# BPB_FM1.net
KiCad netlist of a schematic drawn in EAGLE
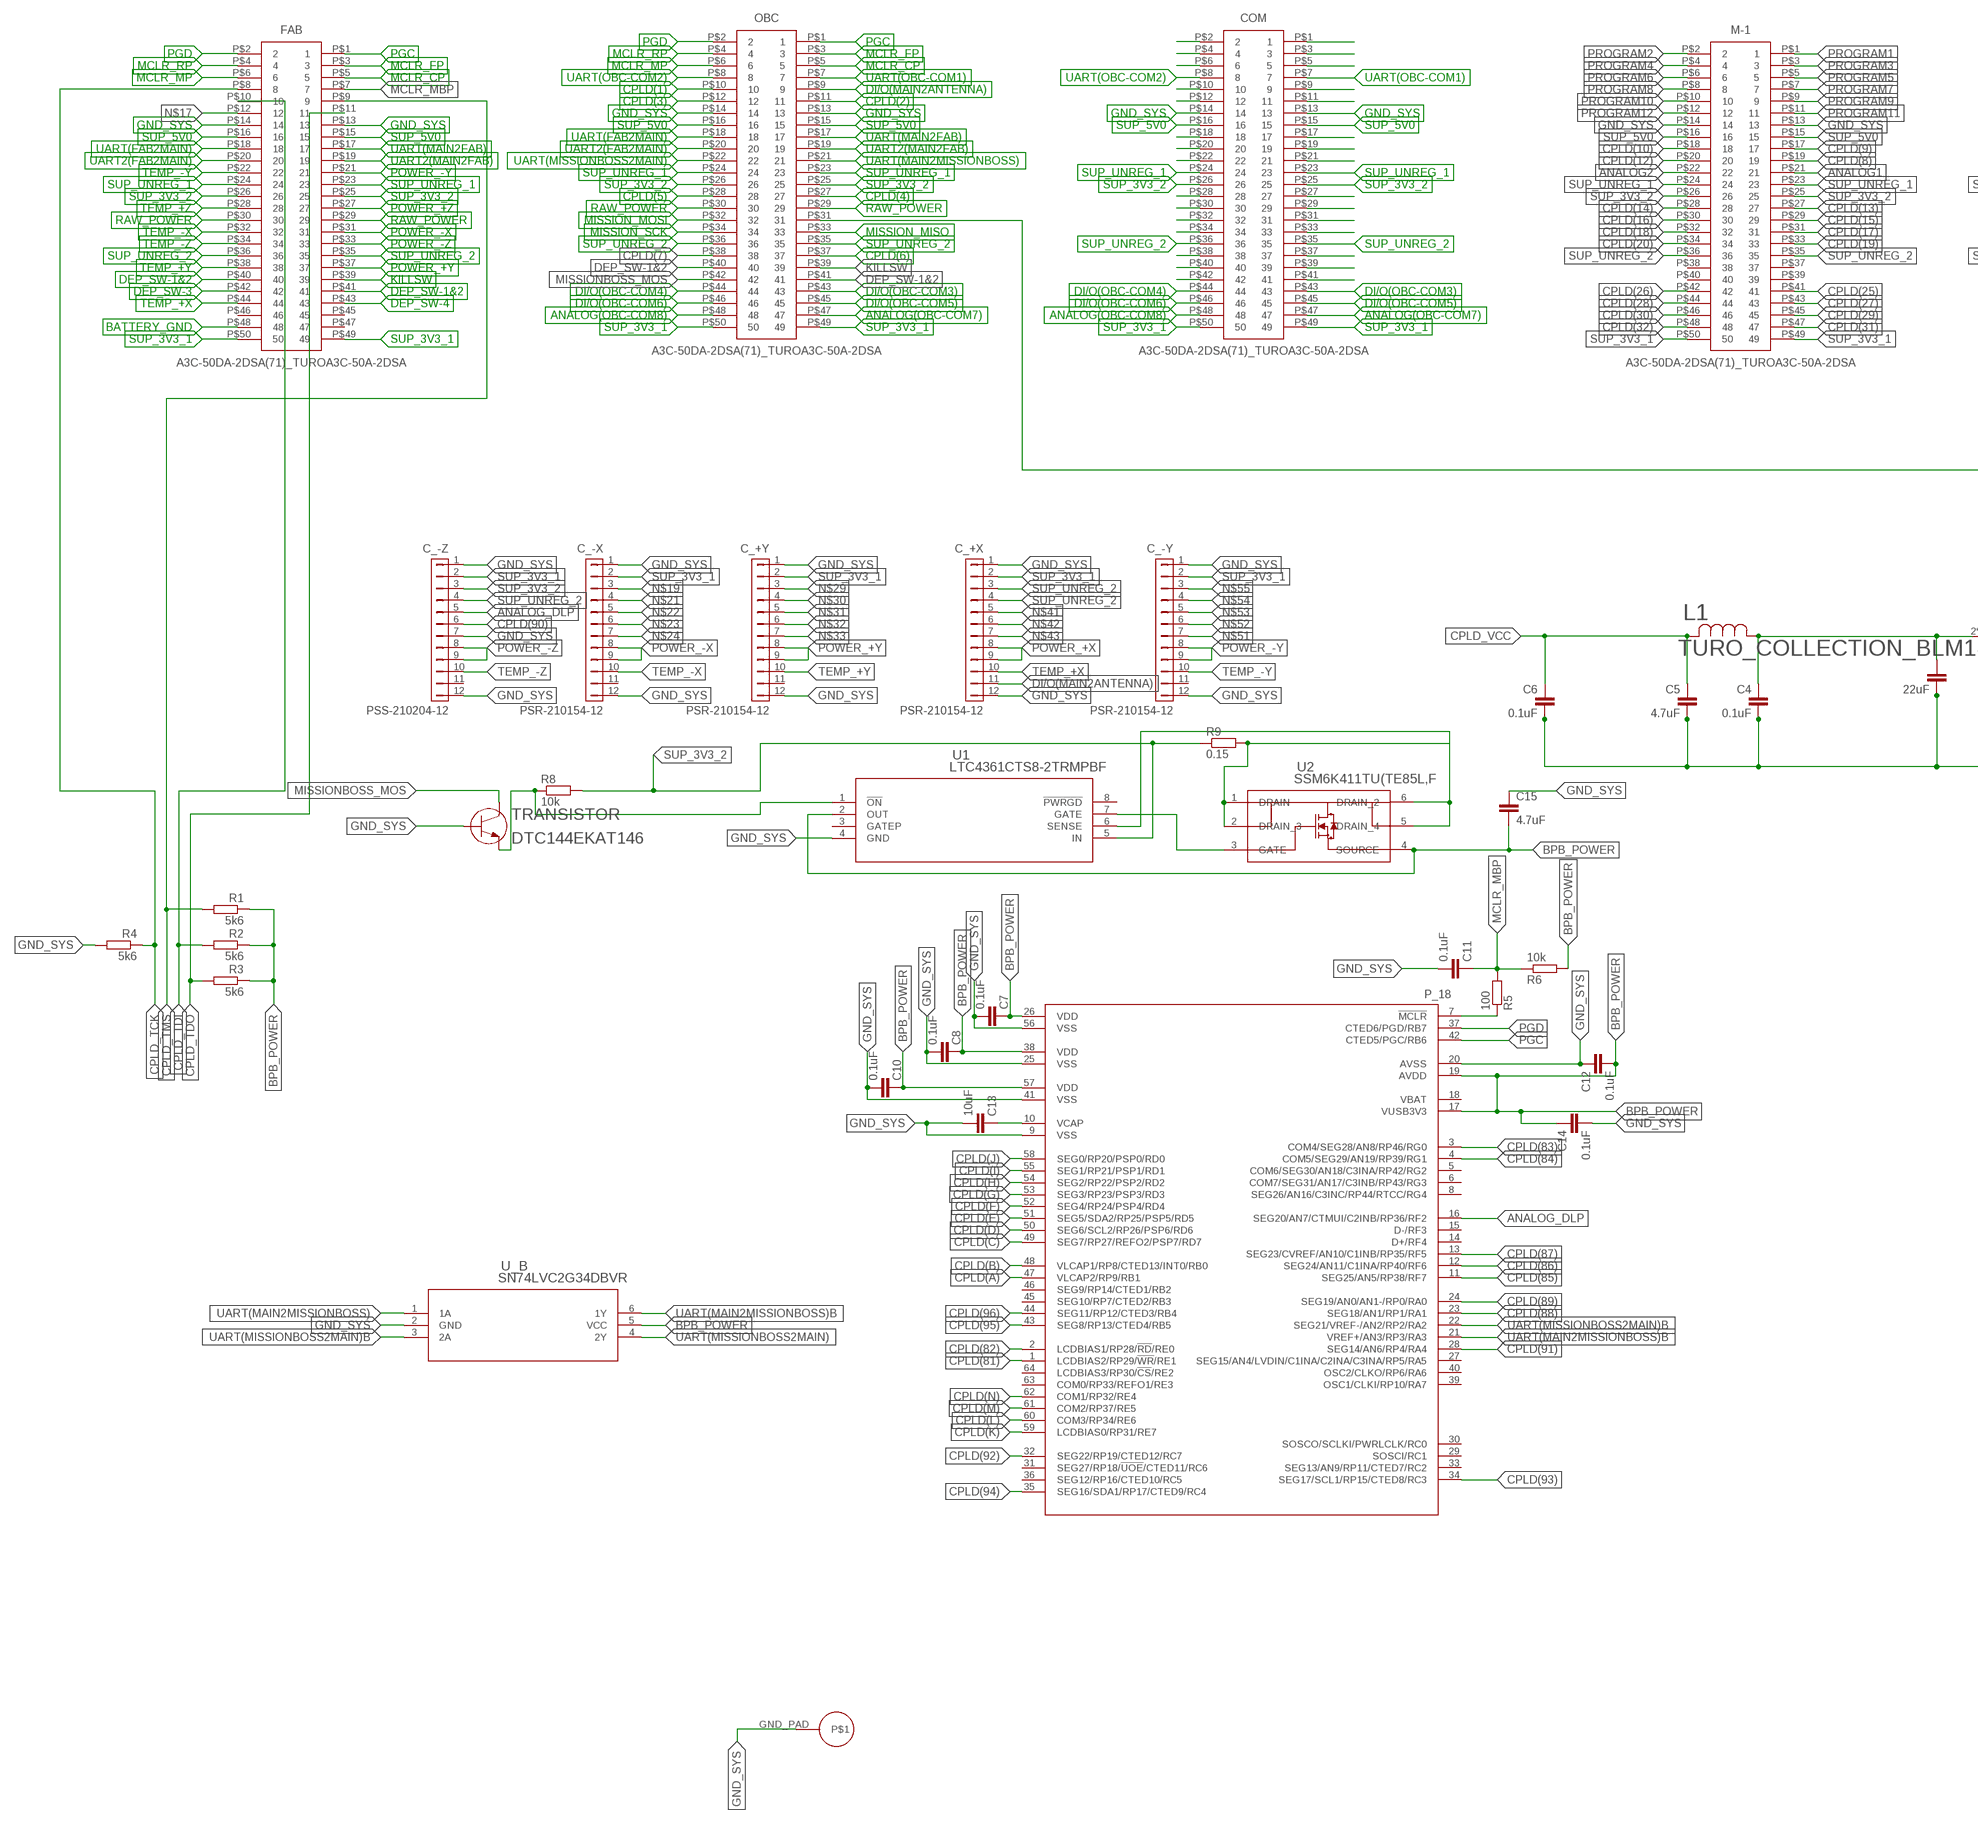
[diagram p0: schematic, sheet 1, part 1 of 2]
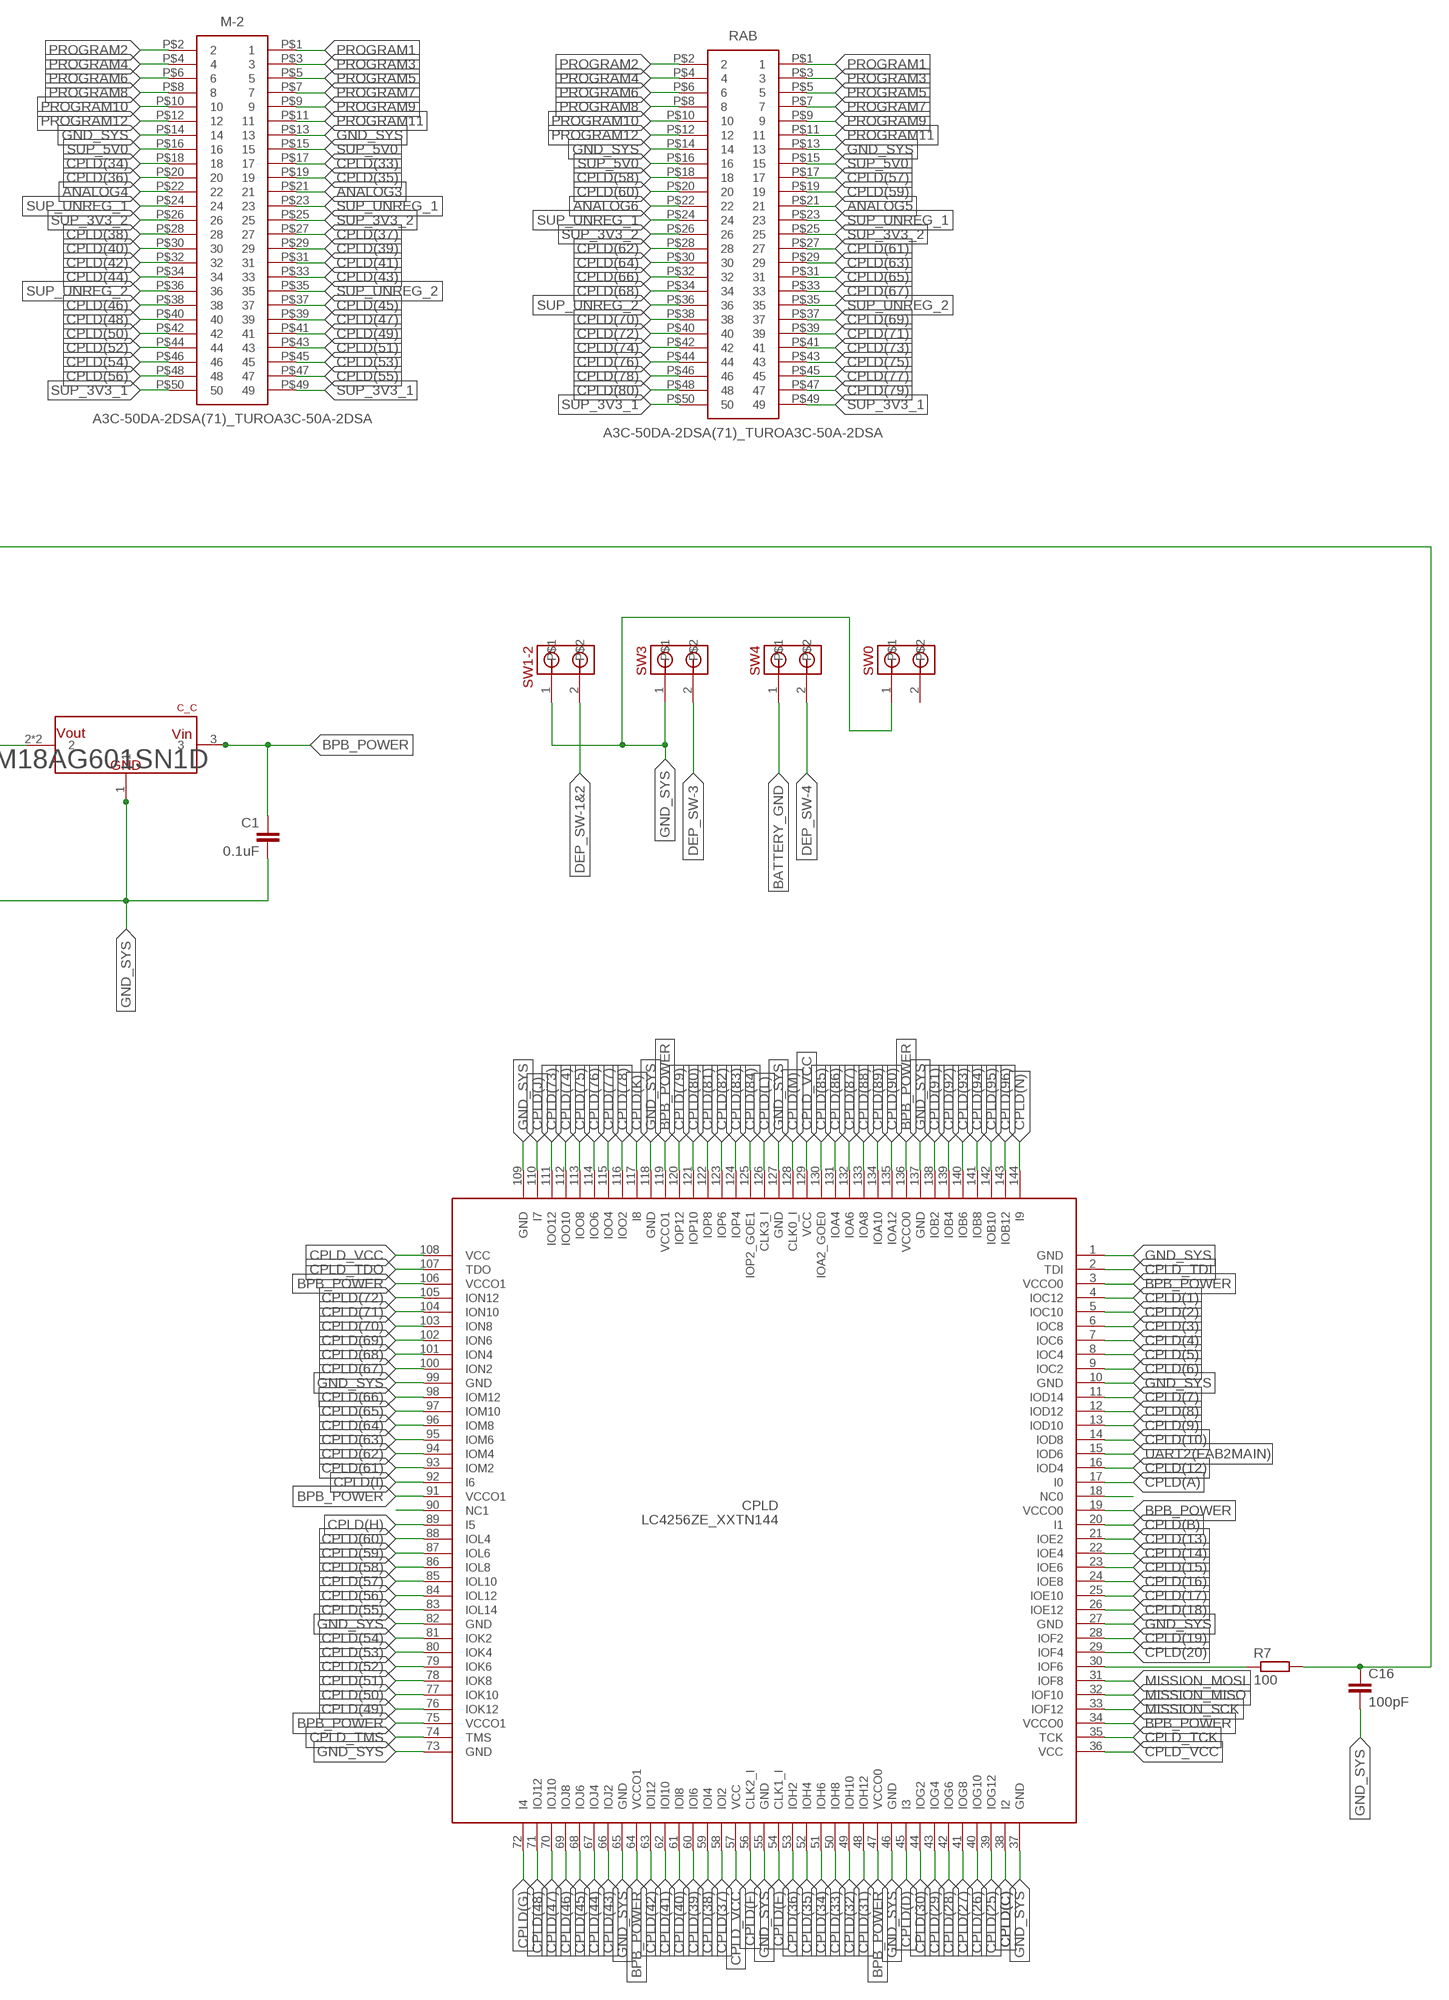
[diagram p1: schematic, sheet 1, part 2 of 2]

(export (version "E")
  (design (tool "Eeschema 10.0.6"))
  (components
    (comp (ref "C1")
      (value "0.1uF")
      (footprint "eagle-import:C0402")
      (libsource (lib "eagle-import") (part "CC0402"))
    )
    (comp (ref "C3")
      (value "22uF")
      (footprint "eagle-import:C2012")
      (libsource (lib "eagle-import") (part "CC2012"))
    )
    (comp (ref "C4")
      (value "0.1uF")
      (footprint "eagle-import:C0402")
      (libsource (lib "eagle-import") (part "CC0402"))
    )
    (comp (ref "C5")
      (value "4.7uF")
      (footprint "eagle-import:C2012")
      (libsource (lib "eagle-import") (part "CC2012"))
    )
    (comp (ref "C6")
      (value "0.1uF")
      (footprint "eagle-import:C0402")
      (libsource (lib "eagle-import") (part "CC0402"))
    )
    (comp (ref "C7")
      (value "0.1uF")
      (footprint "eagle-import:C0402")
      (libsource (lib "eagle-import") (part "CC0402"))
    )
    (comp (ref "C8")
      (value "0.1uF")
      (footprint "eagle-import:C0402")
      (libsource (lib "eagle-import") (part "CC0402"))
    )
    (comp (ref "C10")
      (value "0.1uF")
      (footprint "eagle-import:C0402")
      (libsource (lib "eagle-import") (part "CC0402"))
    )
    (comp (ref "C11")
      (value "0.1uF")
      (footprint "eagle-import:C0402")
      (libsource (lib "eagle-import") (part "CC0402"))
    )
    (comp (ref "C12")
      (value "0.1uF")
      (footprint "eagle-import:C0402")
      (libsource (lib "eagle-import") (part "CC0402"))
    )
    (comp (ref "C13")
      (value "10uF")
      (footprint "eagle-import:C0402")
      (libsource (lib "eagle-import") (part "CC0402"))
    )
    (comp (ref "C14")
      (value "0.1uF")
      (footprint "eagle-import:C0402")
      (libsource (lib "eagle-import") (part "CC0402"))
    )
    (comp (ref "C15")
      (value "4.7uF")
      (footprint "eagle-import:C0402")
      (libsource (lib "eagle-import") (part "CC0402"))
    )
    (comp (ref "C16")
      (value "100pF")
      (footprint "eagle-import:C0402")
      (libsource (lib "eagle-import") (part "CC0402"))
    )
    (comp (ref "COM")
      (value "A3C-50DA-2DSA(71)_TUROA3C-50A-2DSA")
      (footprint "eagle-import:SHDR50W60P200_2X25_5000X400X44_TR")
      (libsource (lib "eagle-import") (part "A3C-50DA-2DSA(71)_TUROA3C-50A-2DSA"))
    )
    (comp (ref "CPLD")
      (value "LC4256ZE_XXTN144")
      (footprint "eagle-import:TQFP144")
      (libsource (lib "eagle-import") (part "LC4256ZE_XXTN144"))
    )
    (comp (ref "C_+X")
      (value "PSR-210154-12")
      (footprint "eagle-import:PIN1X12_90")
      (libsource (lib "eagle-import") (part "PSR-210154-12"))
    )
    (comp (ref "C_+Y")
      (value "PSR-210154-12")
      (footprint "eagle-import:PIN1X12_90")
      (libsource (lib "eagle-import") (part "PSR-210154-12"))
    )
    (comp (ref "C_-X")
      (value "PSR-210154-12")
      (footprint "eagle-import:PIN1X12_90")
      (libsource (lib "eagle-import") (part "PSR-210154-12"))
    )
    (comp (ref "C_-Y")
      (value "PSR-210154-12")
      (footprint "eagle-import:PIN1X12_90")
      (libsource (lib "eagle-import") (part "PSR-210154-12"))
    )
    (comp (ref "C_-Z")
      (value "PSS-210204-12")
      (footprint "eagle-import:PIN1X12")
      (libsource (lib "eagle-import") (part "PSS-210204-12"))
    )
    (comp (ref "C_C")
      (value "NCV1117ST18T3G")
      (footprint "eagle-import:SOT223")
      (libsource (lib "eagle-import") (part "NCV1117ST18T3G"))
    )
    (comp (ref "FAB")
      (value "A3C-50DA-2DSA(71)_TUROA3C-50A-2DSA")
      (footprint "eagle-import:SHDR50W60P200_2X25_5000X400X44_TR")
      (libsource (lib "eagle-import") (part "A3C-50DA-2DSA(71)_TUROA3C-50A-2DSA"))
    )
    (comp (ref "L1")
      (value "TURO_COLLECTION_BLM18AG601SN1D")
      (footprint "eagle-import:TURO_COLLECTION_IND_BLM18_0603")
      (fields (field (name "MANUFACTURER_PART_NUMBER") "BLM18AG601SN1D"))
      (libsource (lib "eagle-import") (part "TURO_COLLECTION_BLM18AG601SN1D"))
    )
    (comp (ref "M-1")
      (value "A3C-50DA-2DSA(71)_TUROA3C-50A-2DSA")
      (footprint "eagle-import:SHDR50W60P200_2X25_5000X400X44_TR")
      (libsource (lib "eagle-import") (part "A3C-50DA-2DSA(71)_TUROA3C-50A-2DSA"))
    )
    (comp (ref "M-2")
      (value "A3C-50DA-2DSA(71)_TUROA3C-50A-2DSA")
      (footprint "eagle-import:SHDR50W60P200_2X25_5000X400X44_TR")
      (libsource (lib "eagle-import") (part "A3C-50DA-2DSA(71)_TUROA3C-50A-2DSA"))
    )
    (comp (ref "OBC")
      (value "A3C-50DA-2DSA(71)_TUROA3C-50A-2DSA")
      (footprint "eagle-import:SHDR50W60P200_2X25_5000X400X44_TR")
      (libsource (lib "eagle-import") (part "A3C-50DA-2DSA(71)_TUROA3C-50A-2DSA"))
    )
    (comp (ref "P_18")
      (value "PIC18F67J94")
      (footprint "eagle-import:PIC18F67J9_SMA_LEAD")
      (libsource (lib "eagle-import") (part "PIC18F67J94"))
    )
    (comp (ref "R1")
      (value "5k6")
      (footprint "eagle-import:R0402")
      (libsource (lib "eagle-import") (part "RR0402"))
    )
    (comp (ref "R2")
      (value "5k6")
      (footprint "eagle-import:R0402")
      (libsource (lib "eagle-import") (part "RR0402"))
    )
    (comp (ref "R3")
      (value "5k6")
      (footprint "eagle-import:R0402")
      (libsource (lib "eagle-import") (part "RR0402"))
    )
    (comp (ref "R4")
      (value "5k6")
      (footprint "eagle-import:R0402")
      (libsource (lib "eagle-import") (part "RR0402"))
    )
    (comp (ref "R5")
      (value "100")
      (footprint "eagle-import:R0402")
      (libsource (lib "eagle-import") (part "RR0402"))
    )
    (comp (ref "R6")
      (value "10k")
      (footprint "eagle-import:R0402")
      (libsource (lib "eagle-import") (part "RR0402"))
    )
    (comp (ref "R7")
      (value "100")
      (footprint "eagle-import:R0402")
      (libsource (lib "eagle-import") (part "RR0402"))
    )
    (comp (ref "R8")
      (value "10k")
      (footprint "eagle-import:R0402")
      (libsource (lib "eagle-import") (part "RR0402"))
    )
    (comp (ref "R9")
      (value "0.15")
      (footprint "eagle-import:R0402")
      (libsource (lib "eagle-import") (part "RR0402"))
    )
    (comp (ref "RAB")
      (value "A3C-50DA-2DSA(71)_TUROA3C-50A-2DSA")
      (footprint "eagle-import:SHDR50W60P200_2X25_5000X400X44_TR")
      (libsource (lib "eagle-import") (part "A3C-50DA-2DSA(71)_TUROA3C-50A-2DSA"))
    )
    (comp (ref "SW0")
      (value "MOLEX-CONN-2-0554600272")
      (footprint "eagle-import:MOLEX-CONN-2-BIRDS")
      (libsource (lib "eagle-import") (part "MOLEX-CONN-2-0554600272"))
    )
    (comp (ref "SW1-2")
      (value "MOLEX-CONN-2-0554600272")
      (footprint "eagle-import:MOLEX-CONN-2-BIRDS")
      (libsource (lib "eagle-import") (part "MOLEX-CONN-2-0554600272"))
    )
    (comp (ref "SW3")
      (value "MOLEX-CONN-2-0554600272")
      (footprint "eagle-import:MOLEX-CONN-2-BIRDS")
      (libsource (lib "eagle-import") (part "MOLEX-CONN-2-0554600272"))
    )
    (comp (ref "SW4")
      (value "MOLEX-CONN-2-0554600272")
      (footprint "eagle-import:MOLEX-CONN-2-BIRDS")
      (libsource (lib "eagle-import") (part "MOLEX-CONN-2-0554600272"))
    )
    (comp (ref "TRANSISTOR")
      (value "DTC144EKAT146")
      (footprint "eagle-import:TRANS_DTA113TKAT_ROM")
      (fields (field (name "COPYRIGHT") "Copyright (C) 2018 Accelerated Designs. All rights reserved"))
      (libsource (lib "eagle-import") (part "DTC144EKAT146"))
    )
    (comp (ref "U$1")
      (value "GND_PAD")
      (footprint "eagle-import:GND_PAD")
      (libsource (lib "eagle-import") (part "GND_PAD"))
    )
    (comp (ref "U1")
      (value "LTC4361CTS8-2TRMPBF")
      (footprint "eagle-import:TSOT-23_TS8_LIT")
      (fields (field (name "MANUFACTURER_PART_NUMBER") "LTC4361CTS8-2#TRMPBF"))
      (libsource (lib "eagle-import") (part "LTC4361CTS8-2TRMPBF"))
    )
    (comp (ref "U2")
      (value "SSM6K411TU(TE85L,F")
      (footprint "eagle-import:SON_E85L,F_TOS")
      (fields (field (name "COPYRIGHT") "Copyright (C) 2018 Accelerated Designs. All rights reserved"))
      (libsource (lib "eagle-import") (part "SSM6K411TU(TE85L,F"))
    )
    (comp (ref "U_B")
      (value "SN74LVC2G34DBVR")
      (footprint "eagle-import:DBV6")
      (fields
        (field (name "GENERIC_PART_NUMBER") "SN74LVC2G34")
        (field (name "MANUFACTURER") "Texas Instruments")
      )
      (libsource (lib "eagle-import") (part "SN74LVC2G34DBVR"))
    )
  )
  (nets
    (net (code "1") (name "ANALOG(OBC-COM7)") (class "Default")
      (node (ref "COM") (pin "P$47") (pinfunction "47_P$47") (pintype "passive"))
      (node (ref "OBC") (pin "P$47") (pinfunction "47_P$47") (pintype "passive"))
    )
    (net (code "2") (name "ANALOG(OBC-COM8)") (class "Default")
      (node (ref "COM") (pin "P$48") (pinfunction "48_P$48") (pintype "passive"))
      (node (ref "OBC") (pin "P$48") (pinfunction "48_P$48") (pintype "passive"))
    )
    (net (code "3") (name "ANALOG1") (class "Default")
      (node (ref "M-1") (pin "P$21") (pinfunction "21_P$21") (pintype "passive"))
    )
    (net (code "4") (name "ANALOG2") (class "Default")
      (node (ref "M-1") (pin "P$22") (pinfunction "22_P$22") (pintype "passive"))
    )
    (net (code "5") (name "ANALOG3") (class "Default")
      (node (ref "M-2") (pin "P$21") (pinfunction "21_P$21") (pintype "passive"))
    )
    (net (code "6") (name "ANALOG4") (class "Default")
      (node (ref "M-2") (pin "P$22") (pinfunction "22_P$22") (pintype "passive"))
    )
    (net (code "7") (name "ANALOG5") (class "Default")
      (node (ref "RAB") (pin "P$21") (pinfunction "21_P$21") (pintype "passive"))
    )
    (net (code "8") (name "ANALOG6") (class "Default")
      (node (ref "RAB") (pin "P$22") (pinfunction "22_P$22") (pintype "passive"))
    )
    (net (code "9") (name "ANALOG_DLP") (class "Default")
      (node (ref "C_-Z") (pin "5") (pinfunction "5_5") (pintype "passive"))
      (node (ref "P_18") (pin "16") (pinfunction "SEG20/AN7/CTMUI/C2INB/RP36/RF2_16") (pintype "bidirectional"))
    )
    (net (code "10") (name "BATTERY_GND") (class "Default")
      (node (ref "FAB") (pin "P$48") (pinfunction "48_P$48") (pintype "passive"))
      (node (ref "SW4") (pin "1") (pinfunction "P$1_1") (pintype "bidirectional"))
    )
    (net (code "11") (name "BPB_POWER") (class "Default")
      (node (ref "C1") (pin "1") (pinfunction "1_1") (pintype "passive"))
      (node (ref "C10") (pin "1") (pinfunction "1_1") (pintype "passive"))
      (node (ref "C12") (pin "2") (pinfunction "2_2") (pintype "passive"))
      (node (ref "C14") (pin "1") (pinfunction "1_1") (pintype "passive"))
      (node (ref "C15") (pin "2") (pinfunction "2_2") (pintype "passive"))
      (node (ref "C7") (pin "1") (pinfunction "1_1") (pintype "passive"))
      (node (ref "C8") (pin "1") (pinfunction "1_1") (pintype "passive"))
      (node (ref "CPLD") (pin "106") (pinfunction "VCCO1_106") (pintype "power_in"))
      (node (ref "CPLD") (pin "119") (pinfunction "VCCO1_119") (pintype "power_in"))
      (node (ref "CPLD") (pin "136") (pinfunction "VCCO0_136") (pintype "power_in"))
      (node (ref "CPLD") (pin "19") (pinfunction "VCCO0_19") (pintype "power_in"))
      (node (ref "CPLD") (pin "3") (pinfunction "VCCO0_3") (pintype "power_in"))
      (node (ref "CPLD") (pin "34") (pinfunction "VCCO0_34") (pintype "power_in"))
      (node (ref "CPLD") (pin "47") (pinfunction "VCCO0_47") (pintype "power_in"))
      (node (ref "CPLD") (pin "64") (pinfunction "VCCO1_64") (pintype "power_in"))
      (node (ref "CPLD") (pin "75") (pinfunction "VCCO1_75") (pintype "power_in"))
      (node (ref "CPLD") (pin "91") (pinfunction "VCCO1_91") (pintype "power_in"))
      (node (ref "C_C") (pin "3") (pinfunction "3_3") (pintype "bidirectional"))
      (node (ref "P_18") (pin "17") (pinfunction "VUSB3V3_17") (pintype "bidirectional"))
      (node (ref "P_18") (pin "19") (pinfunction "AVDD_19") (pintype "bidirectional"))
      (node (ref "P_18") (pin "26") (pinfunction "VDD_26") (pintype "bidirectional"))
      (node (ref "P_18") (pin "38") (pinfunction "VDD_38") (pintype "bidirectional"))
      (node (ref "P_18") (pin "57") (pinfunction "VDD_57") (pintype "bidirectional"))
      (node (ref "R1") (pin "1") (pinfunction "1_1") (pintype "passive"))
      (node (ref "R2") (pin "1") (pinfunction "1_1") (pintype "passive"))
      (node (ref "R3") (pin "1") (pinfunction "1_1") (pintype "passive"))
      (node (ref "R6") (pin "2") (pinfunction "2_2") (pintype "passive"))
      (node (ref "U1") (pin "2") (pinfunction "OUT_2") (pintype "output"))
      (node (ref "U2") (pin "4") (pinfunction "SOURCE_4") (pintype "passive"))
      (node (ref "U_B") (pin "5") (pinfunction "VCC_5") (pintype "power_in"))
    )
    (net (code "12") (name "CPLD(1)") (class "Default")
      (node (ref "CPLD") (pin "4") (pinfunction "IOC12_4") (pintype "bidirectional"))
      (node (ref "OBC") (pin "P$10") (pinfunction "10_P$10") (pintype "passive"))
    )
    (net (code "13") (name "CPLD(2)") (class "Default")
      (node (ref "CPLD") (pin "5") (pinfunction "IOC10_5") (pintype "bidirectional"))
      (node (ref "OBC") (pin "P$11") (pinfunction "11_P$11") (pintype "passive"))
    )
    (net (code "14") (name "CPLD(3)") (class "Default")
      (node (ref "CPLD") (pin "6") (pinfunction "IOC8_6") (pintype "bidirectional"))
      (node (ref "OBC") (pin "P$12") (pinfunction "12_P$12") (pintype "passive"))
    )
    (net (code "15") (name "CPLD(4)") (class "Default")
      (node (ref "CPLD") (pin "7") (pinfunction "IOC6_7") (pintype "bidirectional"))
      (node (ref "OBC") (pin "P$27") (pinfunction "27_P$27") (pintype "passive"))
    )
    (net (code "16") (name "CPLD(5)") (class "Default")
      (node (ref "CPLD") (pin "8") (pinfunction "IOC4_8") (pintype "bidirectional"))
      (node (ref "OBC") (pin "P$28") (pinfunction "28_P$28") (pintype "passive"))
    )
    (net (code "17") (name "CPLD(6)") (class "Default")
      (node (ref "CPLD") (pin "9") (pinfunction "IOC2_9") (pintype "bidirectional"))
      (node (ref "OBC") (pin "P$37") (pinfunction "37_P$37") (pintype "passive"))
    )
    (net (code "18") (name "CPLD(7)") (class "Default")
      (node (ref "CPLD") (pin "11") (pinfunction "IOD14_11") (pintype "bidirectional"))
      (node (ref "OBC") (pin "P$38") (pinfunction "38_P$38") (pintype "passive"))
    )
    (net (code "19") (name "CPLD(8)") (class "Default")
      (node (ref "CPLD") (pin "12") (pinfunction "IOD12_12") (pintype "bidirectional"))
      (node (ref "M-1") (pin "P$19") (pinfunction "19_P$19") (pintype "passive"))
    )
    (net (code "20") (name "CPLD(9)") (class "Default")
      (node (ref "CPLD") (pin "13") (pinfunction "IOD10_13") (pintype "bidirectional"))
      (node (ref "M-1") (pin "P$17") (pinfunction "17_P$17") (pintype "passive"))
    )
    (net (code "21") (name "CPLD(10)") (class "Default")
      (node (ref "CPLD") (pin "14") (pinfunction "IOD8_14") (pintype "bidirectional"))
      (node (ref "M-1") (pin "P$18") (pinfunction "18_P$18") (pintype "passive"))
    )
    (net (code "22") (name "CPLD(12)") (class "Default")
      (node (ref "CPLD") (pin "16") (pinfunction "IOD4_16") (pintype "bidirectional"))
      (node (ref "M-1") (pin "P$20") (pinfunction "20_P$20") (pintype "passive"))
    )
    (net (code "23") (name "CPLD(13)") (class "Default")
      (node (ref "CPLD") (pin "21") (pinfunction "IOE2_21") (pintype "bidirectional"))
      (node (ref "M-1") (pin "P$27") (pinfunction "27_P$27") (pintype "passive"))
    )
    (net (code "24") (name "CPLD(14)") (class "Default")
      (node (ref "CPLD") (pin "22") (pinfunction "IOE4_22") (pintype "bidirectional"))
      (node (ref "M-1") (pin "P$28") (pinfunction "28_P$28") (pintype "passive"))
    )
    (net (code "25") (name "CPLD(15)") (class "Default")
      (node (ref "CPLD") (pin "23") (pinfunction "IOE6_23") (pintype "bidirectional"))
      (node (ref "M-1") (pin "P$29") (pinfunction "29_P$29") (pintype "passive"))
    )
    (net (code "26") (name "CPLD(16)") (class "Default")
      (node (ref "CPLD") (pin "24") (pinfunction "IOE8_24") (pintype "bidirectional"))
      (node (ref "M-1") (pin "P$30") (pinfunction "30_P$30") (pintype "passive"))
    )
    (net (code "27") (name "CPLD(17)") (class "Default")
      (node (ref "CPLD") (pin "25") (pinfunction "IOE10_25") (pintype "bidirectional"))
      (node (ref "M-1") (pin "P$31") (pinfunction "31_P$31") (pintype "passive"))
    )
    (net (code "28") (name "CPLD(18)") (class "Default")
      (node (ref "CPLD") (pin "26") (pinfunction "IOE12_26") (pintype "bidirectional"))
      (node (ref "M-1") (pin "P$32") (pinfunction "32_P$32") (pintype "passive"))
    )
    (net (code "29") (name "CPLD(19)") (class "Default")
      (node (ref "CPLD") (pin "28") (pinfunction "IOF2_28") (pintype "bidirectional"))
      (node (ref "M-1") (pin "P$33") (pinfunction "33_P$33") (pintype "passive"))
    )
    (net (code "30") (name "CPLD(20)") (class "Default")
      (node (ref "CPLD") (pin "29") (pinfunction "IOF4_29") (pintype "bidirectional"))
      (node (ref "M-1") (pin "P$34") (pinfunction "34_P$34") (pintype "passive"))
    )
    (net (code "31") (name "CPLD(25)") (class "Default")
      (node (ref "CPLD") (pin "39") (pinfunction "IOG12_39") (pintype "bidirectional"))
      (node (ref "M-1") (pin "P$41") (pinfunction "41_P$41") (pintype "passive"))
    )
    (net (code "32") (name "CPLD(26)") (class "Default")
      (node (ref "CPLD") (pin "40") (pinfunction "IOG10_40") (pintype "bidirectional"))
      (node (ref "M-1") (pin "P$42") (pinfunction "42_P$42") (pintype "passive"))
    )
    (net (code "33") (name "CPLD(27)") (class "Default")
      (node (ref "CPLD") (pin "41") (pinfunction "IOG8_41") (pintype "bidirectional"))
      (node (ref "M-1") (pin "P$43") (pinfunction "43_P$43") (pintype "passive"))
    )
    (net (code "34") (name "CPLD(28)") (class "Default")
      (node (ref "CPLD") (pin "42") (pinfunction "IOG6_42") (pintype "bidirectional"))
      (node (ref "M-1") (pin "P$44") (pinfunction "44_P$44") (pintype "passive"))
    )
    (net (code "35") (name "CPLD(29)") (class "Default")
      (node (ref "CPLD") (pin "43") (pinfunction "IOG4_43") (pintype "bidirectional"))
      (node (ref "M-1") (pin "P$45") (pinfunction "45_P$45") (pintype "passive"))
    )
    (net (code "36") (name "CPLD(30)") (class "Default")
      (node (ref "CPLD") (pin "44") (pinfunction "IOG2_44") (pintype "bidirectional"))
      (node (ref "M-1") (pin "P$46") (pinfunction "46_P$46") (pintype "passive"))
    )
    (net (code "37") (name "CPLD(31)") (class "Default")
      (node (ref "CPLD") (pin "48") (pinfunction "IOH12_48") (pintype "bidirectional"))
      (node (ref "M-1") (pin "P$47") (pinfunction "47_P$47") (pintype "passive"))
    )
    (net (code "38") (name "CPLD(32)") (class "Default")
      (node (ref "CPLD") (pin "49") (pinfunction "IOH10_49") (pintype "bidirectional"))
      (node (ref "M-1") (pin "P$48") (pinfunction "48_P$48") (pintype "passive"))
    )
    (net (code "39") (name "CPLD(33)") (class "Default")
      (node (ref "CPLD") (pin "50") (pinfunction "IOH8_50") (pintype "bidirectional"))
      (node (ref "M-2") (pin "P$17") (pinfunction "17_P$17") (pintype "passive"))
    )
    (net (code "40") (name "CPLD(34)") (class "Default")
      (node (ref "CPLD") (pin "51") (pinfunction "IOH6_51") (pintype "bidirectional"))
      (node (ref "M-2") (pin "P$18") (pinfunction "18_P$18") (pintype "passive"))
    )
    (net (code "41") (name "CPLD(35)") (class "Default")
      (node (ref "CPLD") (pin "52") (pinfunction "IOH4_52") (pintype "bidirectional"))
      (node (ref "M-2") (pin "P$19") (pinfunction "19_P$19") (pintype "passive"))
    )
    (net (code "42") (name "CPLD(36)") (class "Default")
      (node (ref "CPLD") (pin "53") (pinfunction "IOH2_53") (pintype "bidirectional"))
      (node (ref "M-2") (pin "P$20") (pinfunction "20_P$20") (pintype "passive"))
    )
    (net (code "43") (name "CPLD(37)") (class "Default")
      (node (ref "CPLD") (pin "58") (pinfunction "IOI2_58") (pintype "bidirectional"))
      (node (ref "M-2") (pin "P$27") (pinfunction "27_P$27") (pintype "passive"))
    )
    (net (code "44") (name "CPLD(38)") (class "Default")
      (node (ref "CPLD") (pin "59") (pinfunction "IOI4_59") (pintype "bidirectional"))
      (node (ref "M-2") (pin "P$28") (pinfunction "28_P$28") (pintype "passive"))
    )
    (net (code "45") (name "CPLD(39)") (class "Default")
      (node (ref "CPLD") (pin "60") (pinfunction "IOI6_60") (pintype "bidirectional"))
      (node (ref "M-2") (pin "P$29") (pinfunction "29_P$29") (pintype "passive"))
    )
    (net (code "46") (name "CPLD(40)") (class "Default")
      (node (ref "CPLD") (pin "61") (pinfunction "IOI8_61") (pintype "bidirectional"))
      (node (ref "M-2") (pin "P$30") (pinfunction "30_P$30") (pintype "passive"))
    )
    (net (code "47") (name "CPLD(41)") (class "Default")
      (node (ref "CPLD") (pin "62") (pinfunction "IOI10_62") (pintype "bidirectional"))
      (node (ref "M-2") (pin "P$31") (pinfunction "31_P$31") (pintype "passive"))
    )
    (net (code "48") (name "CPLD(42)") (class "Default")
      (node (ref "CPLD") (pin "63") (pinfunction "IOI12_63") (pintype "bidirectional"))
      (node (ref "M-2") (pin "P$32") (pinfunction "32_P$32") (pintype "passive"))
    )
    (net (code "49") (name "CPLD(43)") (class "Default")
      (node (ref "CPLD") (pin "66") (pinfunction "IOJ2_66") (pintype "bidirectional"))
      (node (ref "M-2") (pin "P$33") (pinfunction "33_P$33") (pintype "passive"))
    )
    (net (code "50") (name "CPLD(44)") (class "Default")
      (node (ref "CPLD") (pin "67") (pinfunction "IOJ4_67") (pintype "bidirectional"))
      (node (ref "M-2") (pin "P$34") (pinfunction "34_P$34") (pintype "passive"))
    )
    (net (code "51") (name "CPLD(45)") (class "Default")
      (node (ref "CPLD") (pin "68") (pinfunction "IOJ6_68") (pintype "bidirectional"))
      (node (ref "M-2") (pin "P$37") (pinfunction "37_P$37") (pintype "passive"))
    )
    (net (code "52") (name "CPLD(46)") (class "Default")
      (node (ref "CPLD") (pin "69") (pinfunction "IOJ8_69") (pintype "bidirectional"))
      (node (ref "M-2") (pin "P$38") (pinfunction "38_P$38") (pintype "passive"))
    )
    (net (code "53") (name "CPLD(47)") (class "Default")
      (node (ref "CPLD") (pin "70") (pinfunction "IOJ10_70") (pintype "bidirectional"))
      (node (ref "M-2") (pin "P$39") (pinfunction "39_P$39") (pintype "passive"))
    )
    (net (code "54") (name "CPLD(48)") (class "Default")
      (node (ref "CPLD") (pin "71") (pinfunction "IOJ12_71") (pintype "bidirectional"))
      (node (ref "M-2") (pin "P$40") (pinfunction "40_P$40") (pintype "passive"))
    )
    (net (code "55") (name "CPLD(49)") (class "Default")
      (node (ref "CPLD") (pin "76") (pinfunction "IOK12_76") (pintype "bidirectional"))
      (node (ref "M-2") (pin "P$41") (pinfunction "41_P$41") (pintype "passive"))
    )
    (net (code "56") (name "CPLD(50)") (class "Default")
      (node (ref "CPLD") (pin "77") (pinfunction "IOK10_77") (pintype "bidirectional"))
      (node (ref "M-2") (pin "P$42") (pinfunction "42_P$42") (pintype "passive"))
    )
    (net (code "57") (name "CPLD(51)") (class "Default")
      (node (ref "CPLD") (pin "78") (pinfunction "IOK8_78") (pintype "bidirectional"))
      (node (ref "M-2") (pin "P$43") (pinfunction "43_P$43") (pintype "passive"))
    )
    (net (code "58") (name "CPLD(52)") (class "Default")
      (node (ref "CPLD") (pin "79") (pinfunction "IOK6_79") (pintype "bidirectional"))
      (node (ref "M-2") (pin "P$44") (pinfunction "44_P$44") (pintype "passive"))
    )
    (net (code "59") (name "CPLD(53)") (class "Default")
      (node (ref "CPLD") (pin "80") (pinfunction "IOK4_80") (pintype "bidirectional"))
      (node (ref "M-2") (pin "P$45") (pinfunction "45_P$45") (pintype "passive"))
    )
    (net (code "60") (name "CPLD(54)") (class "Default")
      (node (ref "CPLD") (pin "81") (pinfunction "IOK2_81") (pintype "bidirectional"))
      (node (ref "M-2") (pin "P$46") (pinfunction "46_P$46") (pintype "passive"))
    )
    (net (code "61") (name "CPLD(55)") (class "Default")
      (node (ref "CPLD") (pin "83") (pinfunction "IOL14_83") (pintype "bidirectional"))
      (node (ref "M-2") (pin "P$47") (pinfunction "47_P$47") (pintype "passive"))
    )
    (net (code "62") (name "CPLD(56)") (class "Default")
      (node (ref "CPLD") (pin "84") (pinfunction "IOL12_84") (pintype "bidirectional"))
      (node (ref "M-2") (pin "P$48") (pinfunction "48_P$48") (pintype "passive"))
    )
    (net (code "63") (name "CPLD(57)") (class "Default")
      (node (ref "CPLD") (pin "85") (pinfunction "IOL10_85") (pintype "bidirectional"))
      (node (ref "RAB") (pin "P$17") (pinfunction "17_P$17") (pintype "passive"))
    )
    (net (code "64") (name "CPLD(58)") (class "Default")
      (node (ref "CPLD") (pin "86") (pinfunction "IOL8_86") (pintype "bidirectional"))
      (node (ref "RAB") (pin "P$18") (pinfunction "18_P$18") (pintype "passive"))
    )
    (net (code "65") (name "CPLD(59)") (class "Default")
      (node (ref "CPLD") (pin "87") (pinfunction "IOL6_87") (pintype "bidirectional"))
      (node (ref "RAB") (pin "P$19") (pinfunction "19_P$19") (pintype "passive"))
    )
    (net (code "66") (name "CPLD(60)") (class "Default")
      (node (ref "CPLD") (pin "88") (pinfunction "IOL4_88") (pintype "bidirectional"))
      (node (ref "RAB") (pin "P$20") (pinfunction "20_P$20") (pintype "passive"))
    )
    (net (code "67") (name "CPLD(61)") (class "Default")
      (node (ref "CPLD") (pin "93") (pinfunction "IOM2_93") (pintype "bidirectional"))
      (node (ref "RAB") (pin "P$27") (pinfunction "27_P$27") (pintype "passive"))
    )
    (net (code "68") (name "CPLD(62)") (class "Default")
      (node (ref "CPLD") (pin "94") (pinfunction "IOM4_94") (pintype "bidirectional"))
      (node (ref "RAB") (pin "P$28") (pinfunction "28_P$28") (pintype "passive"))
    )
    (net (code "69") (name "CPLD(63)") (class "Default")
      (node (ref "CPLD") (pin "95") (pinfunction "IOM6_95") (pintype "bidirectional"))
      (node (ref "RAB") (pin "P$29") (pinfunction "29_P$29") (pintype "passive"))
    )
    (net (code "70") (name "CPLD(64)") (class "Default")
      (node (ref "CPLD") (pin "96") (pinfunction "IOM8_96") (pintype "bidirectional"))
      (node (ref "RAB") (pin "P$30") (pinfunction "30_P$30") (pintype "passive"))
    )
    (net (code "71") (name "CPLD(65)") (class "Default")
      (node (ref "CPLD") (pin "97") (pinfunction "IOM10_97") (pintype "bidirectional"))
      (node (ref "RAB") (pin "P$31") (pinfunction "31_P$31") (pintype "passive"))
    )
    (net (code "72") (name "CPLD(66)") (class "Default")
      (node (ref "CPLD") (pin "98") (pinfunction "IOM12_98") (pintype "bidirectional"))
      (node (ref "RAB") (pin "P$32") (pinfunction "32_P$32") (pintype "passive"))
    )
    (net (code "73") (name "CPLD(67)") (class "Default")
      (node (ref "CPLD") (pin "100") (pinfunction "ION2_100") (pintype "bidirectional"))
      (node (ref "RAB") (pin "P$33") (pinfunction "33_P$33") (pintype "passive"))
    )
    (net (code "74") (name "CPLD(68)") (class "Default")
      (node (ref "CPLD") (pin "101") (pinfunction "ION4_101") (pintype "bidirectional"))
      (node (ref "RAB") (pin "P$34") (pinfunction "34_P$34") (pintype "passive"))
    )
    (net (code "75") (name "CPLD(69)") (class "Default")
      (node (ref "CPLD") (pin "102") (pinfunction "ION6_102") (pintype "bidirectional"))
      (node (ref "RAB") (pin "P$37") (pinfunction "37_P$37") (pintype "passive"))
    )
    (net (code "76") (name "CPLD(70)") (class "Default")
      (node (ref "CPLD") (pin "103") (pinfunction "ION8_103") (pintype "bidirectional"))
      (node (ref "RAB") (pin "P$38") (pinfunction "38_P$38") (pintype "passive"))
    )
    (net (code "77") (name "CPLD(71)") (class "Default")
      (node (ref "CPLD") (pin "104") (pinfunction "ION10_104") (pintype "bidirectional"))
      (node (ref "RAB") (pin "P$39") (pinfunction "39_P$39") (pintype "passive"))
    )
    (net (code "78") (name "CPLD(72)") (class "Default")
      (node (ref "CPLD") (pin "105") (pinfunction "ION12_105") (pintype "bidirectional"))
      (node (ref "RAB") (pin "P$40") (pinfunction "40_P$40") (pintype "passive"))
    )
    (net (code "79") (name "CPLD(73)") (class "Default")
      (node (ref "CPLD") (pin "111") (pinfunction "IOO12_111") (pintype "bidirectional"))
      (node (ref "RAB") (pin "P$41") (pinfunction "41_P$41") (pintype "passive"))
    )
    (net (code "80") (name "CPLD(74)") (class "Default")
      (node (ref "CPLD") (pin "112") (pinfunction "IOO10_112") (pintype "bidirectional"))
      (node (ref "RAB") (pin "P$42") (pinfunction "42_P$42") (pintype "passive"))
    )
    (net (code "81") (name "CPLD(75)") (class "Default")
      (node (ref "CPLD") (pin "113") (pinfunction "IOO8_113") (pintype "bidirectional"))
      (node (ref "RAB") (pin "P$43") (pinfunction "43_P$43") (pintype "passive"))
    )
    (net (code "82") (name "CPLD(76)") (class "Default")
      (node (ref "CPLD") (pin "114") (pinfunction "IOO6_114") (pintype "bidirectional"))
      (node (ref "RAB") (pin "P$44") (pinfunction "44_P$44") (pintype "passive"))
    )
    (net (code "83") (name "CPLD(77)") (class "Default")
      (node (ref "CPLD") (pin "115") (pinfunction "IOO4_115") (pintype "bidirectional"))
      (node (ref "RAB") (pin "P$45") (pinfunction "45_P$45") (pintype "passive"))
    )
    (net (code "84") (name "CPLD(78)") (class "Default")
      (node (ref "CPLD") (pin "116") (pinfunction "IOO2_116") (pintype "bidirectional"))
      (node (ref "RAB") (pin "P$46") (pinfunction "46_P$46") (pintype "passive"))
    )
    (net (code "85") (name "CPLD(79)") (class "Default")
      (node (ref "CPLD") (pin "120") (pinfunction "IOP12_120") (pintype "bidirectional"))
      (node (ref "RAB") (pin "P$47") (pinfunction "47_P$47") (pintype "passive"))
    )
    (net (code "86") (name "CPLD(80)") (class "Default")
      (node (ref "CPLD") (pin "121") (pinfunction "IOP10_121") (pintype "bidirectional"))
      (node (ref "RAB") (pin "P$48") (pinfunction "48_P$48") (pintype "passive"))
    )
    (net (code "87") (name "CPLD(81)") (class "Default")
      (node (ref "CPLD") (pin "122") (pinfunction "IOP8_122") (pintype "bidirectional"))
      (node (ref "P_18") (pin "1") (pinfunction "LCDBIAS2/RP29/~{WR}/RE1_1") (pintype "bidirectional"))
    )
    (net (code "88") (name "CPLD(82)") (class "Default")
      (node (ref "CPLD") (pin "123") (pinfunction "IOP6_123") (pintype "bidirectional"))
      (node (ref "P_18") (pin "2") (pinfunction "LCDBIAS1/RP28/~{RD}/RE0_2") (pintype "bidirectional"))
    )
    (net (code "89") (name "CPLD(83)") (class "Default")
      (node (ref "CPLD") (pin "124") (pinfunction "IOP4_124") (pintype "bidirectional"))
      (node (ref "P_18") (pin "3") (pinfunction "COM4/SEG28/AN8/RP46/RG0_3") (pintype "bidirectional"))
    )
    (net (code "90") (name "CPLD(84)") (class "Default")
      (node (ref "CPLD") (pin "125") (pinfunction "IOP2_GOE1_125") (pintype "bidirectional"))
      (node (ref "P_18") (pin "4") (pinfunction "COM5/SEG29/AN19/RP39/RG1_4") (pintype "bidirectional"))
    )
    (net (code "91") (name "CPLD(85)") (class "Default")
      (node (ref "CPLD") (pin "130") (pinfunction "IOA2_GOE0_130") (pintype "bidirectional"))
      (node (ref "P_18") (pin "11") (pinfunction "SEG25/AN5/RP38/RF7_11") (pintype "bidirectional"))
    )
    (net (code "92") (name "CPLD(86)") (class "Default")
      (node (ref "CPLD") (pin "131") (pinfunction "IOA4_131") (pintype "bidirectional"))
      (node (ref "P_18") (pin "12") (pinfunction "SEG24/AN11/C1INA/RP40/RF6_12") (pintype "bidirectional"))
    )
    (net (code "93") (name "CPLD(87)") (class "Default")
      (node (ref "CPLD") (pin "132") (pinfunction "IOA6_132") (pintype "bidirectional"))
      (node (ref "P_18") (pin "13") (pinfunction "SEG23/CVREF/AN10/C1INB/RP35/RF5_13") (pintype "bidirectional"))
    )
    (net (code "94") (name "CPLD(88)") (class "Default")
      (node (ref "CPLD") (pin "133") (pinfunction "IOA8_133") (pintype "bidirectional"))
      (node (ref "P_18") (pin "23") (pinfunction "SEG18/AN1/RP1/RA1_23") (pintype "bidirectional"))
    )
    (net (code "95") (name "CPLD(89)") (class "Default")
      (node (ref "CPLD") (pin "134") (pinfunction "IOA10_134") (pintype "bidirectional"))
      (node (ref "P_18") (pin "24") (pinfunction "SEG19/AN0/AN1-/RP0/RA0_24") (pintype "bidirectional"))
    )
    (net (code "96") (name "CPLD(90)") (class "Default")
      (node (ref "CPLD") (pin "135") (pinfunction "IOA12_135") (pintype "bidirectional"))
      (node (ref "C_-Z") (pin "6") (pinfunction "6_6") (pintype "passive"))
    )
    (net (code "97") (name "CPLD(91)") (class "Default")
      (node (ref "CPLD") (pin "138") (pinfunction "IOB2_138") (pintype "bidirectional"))
      (node (ref "P_18") (pin "28") (pinfunction "SEG14/AN6/RP4/RA4_28") (pintype "bidirectional"))
    )
    (net (code "98") (name "CPLD(92)") (class "Default")
      (node (ref "CPLD") (pin "139") (pinfunction "IOB4_139") (pintype "bidirectional"))
      (node (ref "P_18") (pin "32") (pinfunction "SEG22/RP19/CTED12/RC7_32") (pintype "bidirectional"))
    )
    (net (code "99") (name "CPLD(93)") (class "Default")
      (node (ref "CPLD") (pin "140") (pinfunction "IOB6_140") (pintype "bidirectional"))
      (node (ref "P_18") (pin "34") (pinfunction "SEG17/SCL1/RP15/CTED8/RC3_34") (pintype "bidirectional"))
    )
    (net (code "100") (name "CPLD(94)") (class "Default")
      (node (ref "CPLD") (pin "141") (pinfunction "IOB8_141") (pintype "bidirectional"))
      (node (ref "P_18") (pin "35") (pinfunction "SEG16/SDA1/RP17/CTED9/RC4_35") (pintype "bidirectional"))
    )
    (net (code "101") (name "CPLD(95)") (class "Default")
      (node (ref "CPLD") (pin "142") (pinfunction "IOB10_142") (pintype "bidirectional"))
      (node (ref "P_18") (pin "43") (pinfunction "SEG8/RP13/CTED4/RB5_43") (pintype "bidirectional"))
    )
    (net (code "102") (name "CPLD(96)") (class "Default")
      (node (ref "CPLD") (pin "143") (pinfunction "IOB12_143") (pintype "bidirectional"))
      (node (ref "P_18") (pin "44") (pinfunction "SEG11/RP12/CTED3/RB4_44") (pintype "bidirectional"))
    )
    (net (code "103") (name "CPLD(A)") (class "Default")
      (node (ref "CPLD") (pin "17") (pinfunction "I0_17") (pintype "bidirectional"))
      (node (ref "P_18") (pin "47") (pinfunction "VLCAP2/RP9/RB1_47") (pintype "bidirectional"))
    )
    (net (code "104") (name "CPLD(B)") (class "Default")
      (node (ref "CPLD") (pin "20") (pinfunction "I1_20") (pintype "bidirectional"))
      (node (ref "P_18") (pin "48") (pinfunction "VLCAP1/RP8/CTED13/INT0/RB0_48") (pintype "bidirectional"))
    )
    (net (code "105") (name "CPLD(C)") (class "Default")
      (node (ref "CPLD") (pin "38") (pinfunction "I2_38") (pintype "bidirectional"))
      (node (ref "P_18") (pin "49") (pinfunction "SEG7/RP27/REFO2/PSP7/RD7_49") (pintype "bidirectional"))
    )
    (net (code "106") (name "CPLD(D)") (class "Default")
      (node (ref "CPLD") (pin "45") (pinfunction "I3_45") (pintype "bidirectional"))
      (node (ref "P_18") (pin "50") (pinfunction "SEG6/SCL2/RP26/PSP6/RD6_50") (pintype "bidirectional"))
    )
    (net (code "107") (name "CPLD(E)") (class "Default")
      (node (ref "CPLD") (pin "54") (pinfunction "CLK1_I_54") (pintype "input"))
      (node (ref "P_18") (pin "51") (pinfunction "SEG5/SDA2/RP25/PSP5/RD5_51") (pintype "bidirectional"))
    )
    (net (code "108") (name "CPLD(F)") (class "Default")
      (node (ref "CPLD") (pin "56") (pinfunction "CLK2_I_56") (pintype "input"))
      (node (ref "P_18") (pin "52") (pinfunction "SEG4/RP24/PSP4/RD4_52") (pintype "bidirectional"))
    )
    (net (code "109") (name "CPLD(G)") (class "Default")
      (node (ref "CPLD") (pin "72") (pinfunction "I4_72") (pintype "bidirectional"))
      (node (ref "P_18") (pin "53") (pinfunction "SEG3/RP23/PSP3/RD3_53") (pintype "bidirectional"))
    )
    (net (code "110") (name "CPLD(H)") (class "Default")
      (node (ref "CPLD") (pin "89") (pinfunction "I5_89") (pintype "bidirectional"))
      (node (ref "P_18") (pin "54") (pinfunction "SEG2/RP22/PSP2/RD2_54") (pintype "bidirectional"))
    )
    (net (code "111") (name "CPLD(I)") (class "Default")
      (node (ref "CPLD") (pin "92") (pinfunction "I6_92") (pintype "bidirectional"))
      (node (ref "P_18") (pin "55") (pinfunction "SEG1/RP21/PSP1/RD1_55") (pintype "bidirectional"))
    )
    (net (code "112") (name "CPLD(J)") (class "Default")
      (node (ref "CPLD") (pin "110") (pinfunction "I7_110") (pintype "bidirectional"))
      (node (ref "P_18") (pin "58") (pinfunction "SEG0/RP20/PSP0/RD0_58") (pintype "bidirectional"))
    )
    (net (code "113") (name "CPLD(K)") (class "Default")
      (node (ref "CPLD") (pin "117") (pinfunction "I8_117") (pintype "bidirectional"))
      (node (ref "P_18") (pin "59") (pinfunction "LCDBIAS0/RP31/RE7_59") (pintype "bidirectional"))
    )
    (net (code "114") (name "CPLD(L)") (class "Default")
      (node (ref "CPLD") (pin "126") (pinfunction "CLK3_I_126") (pintype "input"))
      (node (ref "P_18") (pin "60") (pinfunction "COM3/RP34/RE6_60") (pintype "bidirectional"))
    )
    (net (code "115") (name "CPLD(M)") (class "Default")
      (node (ref "CPLD") (pin "128") (pinfunction "CLK0_I_128") (pintype "input"))
      (node (ref "P_18") (pin "61") (pinfunction "COM2/RP37/RE5_61") (pintype "bidirectional"))
    )
    (net (code "116") (name "CPLD(N)") (class "Default")
      (node (ref "CPLD") (pin "144") (pinfunction "I9_144") (pintype "bidirectional"))
      (node (ref "P_18") (pin "62") (pinfunction "COM1/RP32/RE4_62") (pintype "bidirectional"))
    )
    (net (code "117") (name "CPLD_TCK") (class "Default")
      (node (ref "CPLD") (pin "35") (pinfunction "TCK_35") (pintype "input"))
      (node (ref "FAB") (pin "P$8") (pinfunction "8_P$8") (pintype "passive"))
      (node (ref "R4") (pin "1") (pinfunction "1_1") (pintype "passive"))
    )
    (net (code "118") (name "CPLD_TDI") (class "Default")
      (node (ref "CPLD") (pin "2") (pinfunction "TDI_2") (pintype "input"))
      (node (ref "FAB") (pin "P$10") (pinfunction "10_P$10") (pintype "passive"))
      (node (ref "R2") (pin "2") (pinfunction "2_2") (pintype "passive"))
    )
    (net (code "119") (name "CPLD_TDO") (class "Default")
      (node (ref "CPLD") (pin "107") (pinfunction "TDO_107") (pintype "output"))
      (node (ref "FAB") (pin "P$11") (pinfunction "11_P$11") (pintype "passive"))
      (node (ref "R3") (pin "2") (pinfunction "2_2") (pintype "passive"))
    )
    (net (code "120") (name "CPLD_TMS") (class "Default")
      (node (ref "CPLD") (pin "74") (pinfunction "TMS_74") (pintype "input"))
      (node (ref "FAB") (pin "P$9") (pinfunction "9_P$9") (pintype "passive"))
      (node (ref "R1") (pin "2") (pinfunction "2_2") (pintype "passive"))
    )
    (net (code "121") (name "CPLD_VCC") (class "Default")
      (node (ref "C5") (pin "1") (pinfunction "1_1") (pintype "passive"))
      (node (ref "C6") (pin "1") (pinfunction "1_1") (pintype "passive"))
      (node (ref "CPLD") (pin "108") (pinfunction "VCC_108") (pintype "power_in"))
      (node (ref "CPLD") (pin "129") (pinfunction "VCC_129") (pintype "power_in"))
      (node (ref "CPLD") (pin "36") (pinfunction "VCC_36") (pintype "power_in"))
      (node (ref "CPLD") (pin "57") (pinfunction "VCC_57") (pintype "power_in"))
      (node (ref "L1") (pin "2") (pinfunction "2_2") (pintype "passive"))
    )
    (net (code "122") (name "DEP_SW-1&2") (class "Default")
      (node (ref "FAB") (pin "P$40") (pinfunction "40_P$40") (pintype "passive"))
      (node (ref "FAB") (pin "P$41") (pinfunction "41_P$41") (pintype "passive"))
      (node (ref "OBC") (pin "P$40") (pinfunction "40_P$40") (pintype "passive"))
      (node (ref "OBC") (pin "P$41") (pinfunction "41_P$41") (pintype "passive"))
      (node (ref "SW1-2") (pin "2") (pinfunction "P$2_2") (pintype "bidirectional"))
    )
    (net (code "123") (name "DEP_SW-3") (class "Default")
      (node (ref "FAB") (pin "P$42") (pinfunction "42_P$42") (pintype "passive"))
      (node (ref "SW3") (pin "2") (pinfunction "P$2_2") (pintype "bidirectional"))
    )
    (net (code "124") (name "DEP_SW-4") (class "Default")
      (node (ref "FAB") (pin "P$43") (pinfunction "43_P$43") (pintype "passive"))
      (node (ref "SW4") (pin "2") (pinfunction "P$2_2") (pintype "bidirectional"))
    )
    (net (code "125") (name "DI{slash}O(MAIN2ANTENNA)") (class "Default")
      (node (ref "C_+X") (pin "11") (pinfunction "11_11") (pintype "passive"))
      (node (ref "OBC") (pin "P$9") (pinfunction "9_P$9") (pintype "passive"))
    )
    (net (code "126") (name "DI{slash}O(OBC-COM3)") (class "Default")
      (node (ref "COM") (pin "P$43") (pinfunction "43_P$43") (pintype "passive"))
      (node (ref "OBC") (pin "P$43") (pinfunction "43_P$43") (pintype "passive"))
    )
    (net (code "127") (name "DI{slash}O(OBC-COM4)") (class "Default")
      (node (ref "COM") (pin "P$44") (pinfunction "44_P$44") (pintype "passive"))
      (node (ref "OBC") (pin "P$44") (pinfunction "44_P$44") (pintype "passive"))
    )
    (net (code "128") (name "DI{slash}O(OBC-COM5)") (class "Default")
      (node (ref "COM") (pin "P$45") (pinfunction "45_P$45") (pintype "passive"))
      (node (ref "OBC") (pin "P$45") (pinfunction "45_P$45") (pintype "passive"))
    )
    (net (code "129") (name "DI{slash}O(OBC-COM6)") (class "Default")
      (node (ref "COM") (pin "P$46") (pinfunction "46_P$46") (pintype "passive"))
      (node (ref "OBC") (pin "P$46") (pinfunction "46_P$46") (pintype "passive"))
    )
    (net (code "130") (name "GND_SYS") (class "Default")
      (node (ref "C1") (pin "2") (pinfunction "2_2") (pintype "passive"))
      (node (ref "C10") (pin "2") (pinfunction "2_2") (pintype "passive"))
      (node (ref "C11") (pin "2") (pinfunction "2_2") (pintype "passive"))
      (node (ref "C12") (pin "1") (pinfunction "1_1") (pintype "passive"))
      (node (ref "C13") (pin "2") (pinfunction "2_2") (pintype "passive"))
      (node (ref "C14") (pin "2") (pinfunction "2_2") (pintype "passive"))
      (node (ref "C15") (pin "1") (pinfunction "1_1") (pintype "passive"))
      (node (ref "C16") (pin "2") (pinfunction "2_2") (pintype "passive"))
      (node (ref "C3") (pin "2") (pinfunction "2_2") (pintype "passive"))
      (node (ref "C4") (pin "2") (pinfunction "2_2") (pintype "passive"))
      (node (ref "C5") (pin "2") (pinfunction "2_2") (pintype "passive"))
      (node (ref "C6") (pin "2") (pinfunction "2_2") (pintype "passive"))
      (node (ref "C7") (pin "2") (pinfunction "2_2") (pintype "passive"))
      (node (ref "C8") (pin "2") (pinfunction "2_2") (pintype "passive"))
      (node (ref "COM") (pin "P$13") (pinfunction "13_P$13") (pintype "passive"))
      (node (ref "COM") (pin "P$14") (pinfunction "14_P$14") (pintype "passive"))
      (node (ref "CPLD") (pin "1") (pinfunction "GND_1") (pintype "power_in"))
      (node (ref "CPLD") (pin "10") (pinfunction "GND_10") (pintype "power_in"))
      (node (ref "CPLD") (pin "109") (pinfunction "GND_109") (pintype "power_in"))
      (node (ref "CPLD") (pin "118") (pinfunction "GND_118") (pintype "power_in"))
      (node (ref "CPLD") (pin "127") (pinfunction "GND_127") (pintype "power_in"))
      (node (ref "CPLD") (pin "137") (pinfunction "GND_137") (pintype "power_in"))
      (node (ref "CPLD") (pin "27") (pinfunction "GND_27") (pintype "power_in"))
      (node (ref "CPLD") (pin "37") (pinfunction "GND_37") (pintype "power_in"))
      (node (ref "CPLD") (pin "46") (pinfunction "GND_46") (pintype "power_in"))
      (node (ref "CPLD") (pin "55") (pinfunction "GND_55") (pintype "power_in"))
      (node (ref "CPLD") (pin "65") (pinfunction "GND_65") (pintype "power_in"))
      (node (ref "CPLD") (pin "73") (pinfunction "GND_73") (pintype "power_in"))
      (node (ref "CPLD") (pin "82") (pinfunction "GND_82") (pintype "power_in"))
      (node (ref "CPLD") (pin "99") (pinfunction "GND_99") (pintype "power_in"))
      (node (ref "C_+X") (pin "1") (pinfunction "1_1") (pintype "passive"))
      (node (ref "C_+X") (pin "12") (pinfunction "12_12") (pintype "passive"))
      (node (ref "C_+Y") (pin "1") (pinfunction "1_1") (pintype "passive"))
      (node (ref "C_+Y") (pin "12") (pinfunction "12_12") (pintype "passive"))
      (node (ref "C_-X") (pin "1") (pinfunction "1_1") (pintype "passive"))
      (node (ref "C_-X") (pin "12") (pinfunction "12_12") (pintype "passive"))
      (node (ref "C_-Y") (pin "1") (pinfunction "1_1") (pintype "passive"))
      (node (ref "C_-Y") (pin "12") (pinfunction "12_12") (pintype "passive"))
      (node (ref "C_-Z") (pin "1") (pinfunction "1_1") (pintype "passive"))
      (node (ref "C_-Z") (pin "12") (pinfunction "12_12") (pintype "passive"))
      (node (ref "C_-Z") (pin "7") (pinfunction "7_7") (pintype "passive"))
      (node (ref "C_C") (pin "1") (pinfunction "1_1") (pintype "bidirectional"))
      (node (ref "FAB") (pin "P$13") (pinfunction "13_P$13") (pintype "passive"))
      (node (ref "FAB") (pin "P$14") (pinfunction "14_P$14") (pintype "passive"))
      (node (ref "M-1") (pin "P$13") (pinfunction "13_P$13") (pintype "passive"))
      (node (ref "M-1") (pin "P$14") (pinfunction "14_P$14") (pintype "passive"))
      (node (ref "M-2") (pin "P$13") (pinfunction "13_P$13") (pintype "passive"))
      (node (ref "M-2") (pin "P$14") (pinfunction "14_P$14") (pintype "passive"))
      (node (ref "OBC") (pin "P$13") (pinfunction "13_P$13") (pintype "passive"))
      (node (ref "OBC") (pin "P$14") (pinfunction "14_P$14") (pintype "passive"))
      (node (ref "P_18") (pin "20") (pinfunction "AVSS_20") (pintype "bidirectional"))
      (node (ref "P_18") (pin "25") (pinfunction "VSS_25") (pintype "bidirectional"))
      (node (ref "P_18") (pin "41") (pinfunction "VSS_41") (pintype "bidirectional"))
      (node (ref "P_18") (pin "56") (pinfunction "VSS_56") (pintype "bidirectional"))
      (node (ref "P_18") (pin "9") (pinfunction "VSS_9") (pintype "bidirectional"))
      (node (ref "R4") (pin "2") (pinfunction "2_2") (pintype "passive"))
      (node (ref "RAB") (pin "P$13") (pinfunction "13_P$13") (pintype "passive"))
      (node (ref "RAB") (pin "P$14") (pinfunction "14_P$14") (pintype "passive"))
      (node (ref "SW0") (pin "1") (pinfunction "P$1_1") (pintype "bidirectional"))
      (node (ref "SW1-2") (pin "1") (pinfunction "P$1_1") (pintype "bidirectional"))
      (node (ref "SW3") (pin "1") (pinfunction "P$1_1") (pintype "bidirectional"))
      (node (ref "TRANSISTOR") (pin "2") (pinfunction "11_2") (pintype "passive"))
      (node (ref "U$1") (pin "GND_PAD") (pinfunction "P$1_GND_PAD") (pintype "bidirectional"))
      (node (ref "U1") (pin "4") (pinfunction "GND_4") (pintype "power_in"))
      (node (ref "U_B") (pin "2") (pinfunction "GND_2") (pintype "power_in"))
    )
    (net (code "131") (name "KILLSW") (class "Default")
      (node (ref "FAB") (pin "P$39") (pinfunction "39_P$39") (pintype "passive"))
      (node (ref "OBC") (pin "P$39") (pinfunction "39_P$39") (pintype "passive"))
    )
    (net (code "132") (name "MCLR_CP") (class "Default")
      (node (ref "FAB") (pin "P$5") (pinfunction "5_P$5") (pintype "passive"))
      (node (ref "OBC") (pin "P$5") (pinfunction "5_P$5") (pintype "passive"))
    )
    (net (code "133") (name "MCLR_FP") (class "Default")
      (node (ref "FAB") (pin "P$3") (pinfunction "3_P$3") (pintype "passive"))
      (node (ref "OBC") (pin "P$3") (pinfunction "3_P$3") (pintype "passive"))
    )
    (net (code "134") (name "MCLR_MBP") (class "Default")
      (node (ref "C11") (pin "1") (pinfunction "1_1") (pintype "passive"))
      (node (ref "FAB") (pin "P$7") (pinfunction "7_P$7") (pintype "passive"))
      (node (ref "R5") (pin "2") (pinfunction "2_2") (pintype "passive"))
      (node (ref "R6") (pin "1") (pinfunction "1_1") (pintype "passive"))
    )
    (net (code "135") (name "MCLR_MP") (class "Default")
      (node (ref "FAB") (pin "P$6") (pinfunction "6_P$6") (pintype "passive"))
      (node (ref "OBC") (pin "P$6") (pinfunction "6_P$6") (pintype "passive"))
    )
    (net (code "136") (name "MCLR_RP") (class "Default")
      (node (ref "FAB") (pin "P$4") (pinfunction "4_P$4") (pintype "passive"))
      (node (ref "OBC") (pin "P$4") (pinfunction "4_P$4") (pintype "passive"))
    )
    (net (code "137") (name "MISSIONBOSS_MOS") (class "Default")
      (node (ref "OBC") (pin "P$42") (pinfunction "42_P$42") (pintype "passive"))
      (node (ref "TRANSISTOR") (pin "1") (pinfunction "12_1") (pintype "passive"))
    )
    (net (code "138") (name "MISSION_MISO") (class "Default")
      (node (ref "CPLD") (pin "32") (pinfunction "IOF10_32") (pintype "bidirectional"))
      (node (ref "OBC") (pin "P$33") (pinfunction "33_P$33") (pintype "passive"))
    )
    (net (code "139") (name "MISSION_MOSI") (class "Default")
      (node (ref "CPLD") (pin "31") (pinfunction "IOF8_31") (pintype "bidirectional"))
      (node (ref "OBC") (pin "P$32") (pinfunction "32_P$32") (pintype "passive"))
    )
    (net (code "140") (name "MISSION_SCK") (class "Default")
      (node (ref "CPLD") (pin "33") (pinfunction "IOF12_33") (pintype "bidirectional"))
      (node (ref "OBC") (pin "P$34") (pinfunction "34_P$34") (pintype "passive"))
    )
    (net (code "141") (name "N$17") (class "Default")
      (node (ref "FAB") (pin "P$12") (pinfunction "12_P$12") (pintype "passive"))
    )
    (net (code "142") (name "N$19") (class "Default")
      (node (ref "C_-X") (pin "3") (pinfunction "3_3") (pintype "passive"))
    )
    (net (code "143") (name "N$21") (class "Default")
      (node (ref "C_-X") (pin "4") (pinfunction "4_4") (pintype "passive"))
    )
    (net (code "144") (name "N$22") (class "Default")
      (node (ref "C_-X") (pin "5") (pinfunction "5_5") (pintype "passive"))
    )
    (net (code "145") (name "N$23") (class "Default")
      (node (ref "C_-X") (pin "6") (pinfunction "6_6") (pintype "passive"))
    )
    (net (code "146") (name "N$24") (class "Default")
      (node (ref "C_-X") (pin "7") (pinfunction "7_7") (pintype "passive"))
    )
    (net (code "147") (name "N$29") (class "Default")
      (node (ref "C_+Y") (pin "3") (pinfunction "3_3") (pintype "passive"))
    )
    (net (code "148") (name "N$30") (class "Default")
      (node (ref "C_+Y") (pin "4") (pinfunction "4_4") (pintype "passive"))
    )
    (net (code "149") (name "N$31") (class "Default")
      (node (ref "C_+Y") (pin "5") (pinfunction "5_5") (pintype "passive"))
    )
    (net (code "150") (name "N$32") (class "Default")
      (node (ref "C_+Y") (pin "6") (pinfunction "6_6") (pintype "passive"))
    )
    (net (code "151") (name "N$33") (class "Default")
      (node (ref "C_+Y") (pin "7") (pinfunction "7_7") (pintype "passive"))
    )
    (net (code "152") (name "N$41") (class "Default")
      (node (ref "C_+X") (pin "5") (pinfunction "5_5") (pintype "passive"))
    )
    (net (code "153") (name "N$42") (class "Default")
      (node (ref "C_+X") (pin "6") (pinfunction "6_6") (pintype "passive"))
    )
    (net (code "154") (name "N$43") (class "Default")
      (node (ref "C_+X") (pin "7") (pinfunction "7_7") (pintype "passive"))
    )
    (net (code "155") (name "N$51") (class "Default")
      (node (ref "C_-Y") (pin "7") (pinfunction "7_7") (pintype "passive"))
    )
    (net (code "156") (name "N$52") (class "Default")
      (node (ref "C_-Y") (pin "6") (pinfunction "6_6") (pintype "passive"))
    )
    (net (code "157") (name "N$53") (class "Default")
      (node (ref "C_-Y") (pin "5") (pinfunction "5_5") (pintype "passive"))
    )
    (net (code "158") (name "N$54") (class "Default")
      (node (ref "C_-Y") (pin "4") (pinfunction "4_4") (pintype "passive"))
    )
    (net (code "159") (name "N$55") (class "Default")
      (node (ref "C_-Y") (pin "3") (pinfunction "3_3") (pintype "passive"))
    )
    (net (code "160") (name "Net-(C3-Pad1)") (class "Default")
      (node (ref "C3") (pin "1") (pinfunction "1_1") (pintype "passive"))
      (node (ref "C4") (pin "1") (pinfunction "1_1") (pintype "passive"))
      (node (ref "C_C") (pin "2") (pinfunction "2_2") (pintype "bidirectional"))
      (node (ref "C_C") (pin "4") (pinfunction "2_4") (pintype "bidirectional"))
      (node (ref "L1") (pin "1") (pinfunction "1_1") (pintype "passive"))
    )
    (net (code "161") (name "Net-(CPLD-IOF6)") (class "Default")
      (node (ref "CPLD") (pin "30") (pinfunction "IOF6_30") (pintype "bidirectional"))
      (node (ref "R7") (pin "1") (pinfunction "1_1") (pintype "passive"))
    )
    (net (code "162") (name "Net-(OBC-31)") (class "Default")
      (node (ref "C16") (pin "1") (pinfunction "1_1") (pintype "passive"))
      (node (ref "OBC") (pin "P$31") (pinfunction "31_P$31") (pintype "passive"))
      (node (ref "R7") (pin "2") (pinfunction "2_2") (pintype "passive"))
    )
    (net (code "163") (name "Net-(P_18-VCAP)") (class "Default")
      (node (ref "C13") (pin "1") (pinfunction "1_1") (pintype "passive"))
      (node (ref "P_18") (pin "10") (pinfunction "VCAP_10") (pintype "bidirectional"))
    )
    (net (code "164") (name "Net-(P_18-~{MCLR})") (class "Default")
      (node (ref "P_18") (pin "7") (pinfunction "~{MCLR}_7") (pintype "bidirectional"))
      (node (ref "R5") (pin "1") (pinfunction "1_1") (pintype "passive"))
    )
    (net (code "165") (name "Net-(TRANSISTOR-13)") (class "Default")
      (node (ref "R8") (pin "1") (pinfunction "1_1") (pintype "passive"))
      (node (ref "TRANSISTOR") (pin "3") (pinfunction "13_3") (pintype "passive"))
      (node (ref "U1") (pin "1") (pinfunction "~{ON}_1") (pintype "input"))
    )
    (net (code "166") (name "Net-(U1-GATE)") (class "Default")
      (node (ref "U1") (pin "7") (pinfunction "GATE_7") (pintype "passive"))
      (node (ref "U2") (pin "3") (pinfunction "GATE_3") (pintype "passive"))
    )
    (net (code "167") (name "Net-(U1-SENSE)") (class "Default")
      (node (ref "R9") (pin "2") (pinfunction "2_2") (pintype "passive"))
      (node (ref "U1") (pin "6") (pinfunction "SENSE_6") (pintype "input"))
      (node (ref "U2") (pin "1") (pinfunction "DRAIN_1") (pintype "passive"))
      (node (ref "U2") (pin "2") (pinfunction "DRAIN_3_2") (pintype "passive"))
      (node (ref "U2") (pin "5") (pinfunction "DRAIN_4_5") (pintype "passive"))
      (node (ref "U2") (pin "6") (pinfunction "DRAIN_2_6") (pintype "passive"))
    )
    (net (code "168") (name "PGC") (class "Default")
      (node (ref "FAB") (pin "P$1") (pinfunction "1_P$1") (pintype "passive"))
      (node (ref "OBC") (pin "P$1") (pinfunction "1_P$1") (pintype "passive"))
      (node (ref "P_18") (pin "42") (pinfunction "CTED5/PGC/RB6_42") (pintype "bidirectional"))
    )
    (net (code "169") (name "PGD") (class "Default")
      (node (ref "FAB") (pin "P$2") (pinfunction "2_P$2") (pintype "passive"))
      (node (ref "OBC") (pin "P$2") (pinfunction "2_P$2") (pintype "passive"))
      (node (ref "P_18") (pin "37") (pinfunction "CTED6/PGD/RB7_37") (pintype "bidirectional"))
    )
    (net (code "170") (name "POWER_+X") (class "Default")
      (node (ref "C_+X") (pin "8") (pinfunction "8_8") (pintype "passive"))
      (node (ref "C_+X") (pin "9") (pinfunction "9_9") (pintype "passive"))
    )
    (net (code "171") (name "POWER_+Y") (class "Default")
      (node (ref "C_+Y") (pin "8") (pinfunction "8_8") (pintype "passive"))
      (node (ref "C_+Y") (pin "9") (pinfunction "9_9") (pintype "passive"))
      (node (ref "FAB") (pin "P$37") (pinfunction "37_P$37") (pintype "passive"))
    )
    (net (code "172") (name "POWER_+Z") (class "Default")
      (node (ref "FAB") (pin "P$27") (pinfunction "27_P$27") (pintype "passive"))
    )
    (net (code "173") (name "POWER_-X") (class "Default")
      (node (ref "C_-X") (pin "8") (pinfunction "8_8") (pintype "passive"))
      (node (ref "C_-X") (pin "9") (pinfunction "9_9") (pintype "passive"))
      (node (ref "FAB") (pin "P$31") (pinfunction "31_P$31") (pintype "passive"))
    )
    (net (code "174") (name "POWER_-Y") (class "Default")
      (node (ref "C_-Y") (pin "8") (pinfunction "8_8") (pintype "passive"))
      (node (ref "C_-Y") (pin "9") (pinfunction "9_9") (pintype "passive"))
      (node (ref "FAB") (pin "P$21") (pinfunction "21_P$21") (pintype "passive"))
    )
    (net (code "175") (name "POWER_-Z") (class "Default")
      (node (ref "C_-Z") (pin "8") (pinfunction "8_8") (pintype "passive"))
      (node (ref "C_-Z") (pin "9") (pinfunction "9_9") (pintype "passive"))
      (node (ref "FAB") (pin "P$33") (pinfunction "33_P$33") (pintype "passive"))
    )
    (net (code "176") (name "PROGRAM1") (class "Default")
      (node (ref "M-1") (pin "P$1") (pinfunction "1_P$1") (pintype "passive"))
      (node (ref "M-2") (pin "P$1") (pinfunction "1_P$1") (pintype "passive"))
      (node (ref "RAB") (pin "P$1") (pinfunction "1_P$1") (pintype "passive"))
    )
    (net (code "177") (name "PROGRAM2") (class "Default")
      (node (ref "M-1") (pin "P$2") (pinfunction "2_P$2") (pintype "passive"))
      (node (ref "M-2") (pin "P$2") (pinfunction "2_P$2") (pintype "passive"))
      (node (ref "RAB") (pin "P$2") (pinfunction "2_P$2") (pintype "passive"))
    )
    (net (code "178") (name "PROGRAM3") (class "Default")
      (node (ref "M-1") (pin "P$3") (pinfunction "3_P$3") (pintype "passive"))
      (node (ref "M-2") (pin "P$3") (pinfunction "3_P$3") (pintype "passive"))
      (node (ref "RAB") (pin "P$3") (pinfunction "3_P$3") (pintype "passive"))
    )
    (net (code "179") (name "PROGRAM4") (class "Default")
      (node (ref "M-1") (pin "P$4") (pinfunction "4_P$4") (pintype "passive"))
      (node (ref "M-2") (pin "P$4") (pinfunction "4_P$4") (pintype "passive"))
      (node (ref "RAB") (pin "P$4") (pinfunction "4_P$4") (pintype "passive"))
    )
    (net (code "180") (name "PROGRAM5") (class "Default")
      (node (ref "M-1") (pin "P$5") (pinfunction "5_P$5") (pintype "passive"))
      (node (ref "M-2") (pin "P$5") (pinfunction "5_P$5") (pintype "passive"))
      (node (ref "RAB") (pin "P$5") (pinfunction "5_P$5") (pintype "passive"))
    )
    (net (code "181") (name "PROGRAM6") (class "Default")
      (node (ref "M-1") (pin "P$6") (pinfunction "6_P$6") (pintype "passive"))
      (node (ref "M-2") (pin "P$6") (pinfunction "6_P$6") (pintype "passive"))
      (node (ref "RAB") (pin "P$6") (pinfunction "6_P$6") (pintype "passive"))
    )
    (net (code "182") (name "PROGRAM7") (class "Default")
      (node (ref "M-1") (pin "P$7") (pinfunction "7_P$7") (pintype "passive"))
      (node (ref "M-2") (pin "P$7") (pinfunction "7_P$7") (pintype "passive"))
      (node (ref "RAB") (pin "P$7") (pinfunction "7_P$7") (pintype "passive"))
    )
    (net (code "183") (name "PROGRAM8") (class "Default")
      (node (ref "M-1") (pin "P$8") (pinfunction "8_P$8") (pintype "passive"))
      (node (ref "M-2") (pin "P$8") (pinfunction "8_P$8") (pintype "passive"))
      (node (ref "RAB") (pin "P$8") (pinfunction "8_P$8") (pintype "passive"))
    )
    (net (code "184") (name "PROGRAM9") (class "Default")
      (node (ref "M-1") (pin "P$9") (pinfunction "9_P$9") (pintype "passive"))
      (node (ref "M-2") (pin "P$9") (pinfunction "9_P$9") (pintype "passive"))
      (node (ref "RAB") (pin "P$9") (pinfunction "9_P$9") (pintype "passive"))
    )
    (net (code "185") (name "PROGRAM10") (class "Default")
      (node (ref "M-1") (pin "P$10") (pinfunction "10_P$10") (pintype "passive"))
      (node (ref "M-2") (pin "P$10") (pinfunction "10_P$10") (pintype "passive"))
      (node (ref "RAB") (pin "P$10") (pinfunction "10_P$10") (pintype "passive"))
    )
    (net (code "186") (name "PROGRAM11") (class "Default")
      (node (ref "M-1") (pin "P$11") (pinfunction "11_P$11") (pintype "passive"))
      (node (ref "M-2") (pin "P$11") (pinfunction "11_P$11") (pintype "passive"))
      (node (ref "RAB") (pin "P$11") (pinfunction "11_P$11") (pintype "passive"))
    )
    (net (code "187") (name "PROGRAM12") (class "Default")
      (node (ref "M-1") (pin "P$12") (pinfunction "12_P$12") (pintype "passive"))
      (node (ref "M-2") (pin "P$12") (pinfunction "12_P$12") (pintype "passive"))
      (node (ref "RAB") (pin "P$12") (pinfunction "12_P$12") (pintype "passive"))
    )
    (net (code "188") (name "RAW_POWER") (class "Default")
      (node (ref "FAB") (pin "P$29") (pinfunction "29_P$29") (pintype "passive"))
      (node (ref "FAB") (pin "P$30") (pinfunction "30_P$30") (pintype "passive"))
      (node (ref "OBC") (pin "P$29") (pinfunction "29_P$29") (pintype "passive"))
      (node (ref "OBC") (pin "P$30") (pinfunction "30_P$30") (pintype "passive"))
    )
    (net (code "189") (name "SUP_3V3_1") (class "Default")
      (node (ref "COM") (pin "P$49") (pinfunction "49_P$49") (pintype "passive"))
      (node (ref "COM") (pin "P$50") (pinfunction "50_P$50") (pintype "passive"))
      (node (ref "C_+X") (pin "2") (pinfunction "2_2") (pintype "passive"))
      (node (ref "C_+Y") (pin "2") (pinfunction "2_2") (pintype "passive"))
      (node (ref "C_-X") (pin "2") (pinfunction "2_2") (pintype "passive"))
      (node (ref "C_-Y") (pin "2") (pinfunction "2_2") (pintype "passive"))
      (node (ref "C_-Z") (pin "2") (pinfunction "2_2") (pintype "passive"))
      (node (ref "FAB") (pin "P$49") (pinfunction "49_P$49") (pintype "passive"))
      (node (ref "FAB") (pin "P$50") (pinfunction "50_P$50") (pintype "passive"))
      (node (ref "M-1") (pin "P$49") (pinfunction "49_P$49") (pintype "passive"))
      (node (ref "M-1") (pin "P$50") (pinfunction "50_P$50") (pintype "passive"))
      (node (ref "M-2") (pin "P$49") (pinfunction "49_P$49") (pintype "passive"))
      (node (ref "M-2") (pin "P$50") (pinfunction "50_P$50") (pintype "passive"))
      (node (ref "OBC") (pin "P$49") (pinfunction "49_P$49") (pintype "passive"))
      (node (ref "OBC") (pin "P$50") (pinfunction "50_P$50") (pintype "passive"))
      (node (ref "RAB") (pin "P$49") (pinfunction "49_P$49") (pintype "passive"))
      (node (ref "RAB") (pin "P$50") (pinfunction "50_P$50") (pintype "passive"))
    )
    (net (code "190") (name "SUP_3V3_2") (class "Default")
      (node (ref "COM") (pin "P$25") (pinfunction "25_P$25") (pintype "passive"))
      (node (ref "COM") (pin "P$26") (pinfunction "26_P$26") (pintype "passive"))
      (node (ref "C_-Z") (pin "3") (pinfunction "3_3") (pintype "passive"))
      (node (ref "FAB") (pin "P$25") (pinfunction "25_P$25") (pintype "passive"))
      (node (ref "FAB") (pin "P$26") (pinfunction "26_P$26") (pintype "passive"))
      (node (ref "M-1") (pin "P$25") (pinfunction "25_P$25") (pintype "passive"))
      (node (ref "M-1") (pin "P$26") (pinfunction "26_P$26") (pintype "passive"))
      (node (ref "M-2") (pin "P$25") (pinfunction "25_P$25") (pintype "passive"))
      (node (ref "M-2") (pin "P$26") (pinfunction "26_P$26") (pintype "passive"))
      (node (ref "OBC") (pin "P$25") (pinfunction "25_P$25") (pintype "passive"))
      (node (ref "OBC") (pin "P$26") (pinfunction "26_P$26") (pintype "passive"))
      (node (ref "R8") (pin "2") (pinfunction "2_2") (pintype "passive"))
      (node (ref "R9") (pin "1") (pinfunction "1_1") (pintype "passive"))
      (node (ref "RAB") (pin "P$25") (pinfunction "25_P$25") (pintype "passive"))
      (node (ref "RAB") (pin "P$26") (pinfunction "26_P$26") (pintype "passive"))
      (node (ref "U1") (pin "5") (pinfunction "IN_5") (pintype "input"))
    )
    (net (code "191") (name "SUP_5V0") (class "Default")
      (node (ref "COM") (pin "P$15") (pinfunction "15_P$15") (pintype "passive"))
      (node (ref "COM") (pin "P$16") (pinfunction "16_P$16") (pintype "passive"))
      (node (ref "FAB") (pin "P$15") (pinfunction "15_P$15") (pintype "passive"))
      (node (ref "FAB") (pin "P$16") (pinfunction "16_P$16") (pintype "passive"))
      (node (ref "M-1") (pin "P$15") (pinfunction "15_P$15") (pintype "passive"))
      (node (ref "M-1") (pin "P$16") (pinfunction "16_P$16") (pintype "passive"))
      (node (ref "M-2") (pin "P$15") (pinfunction "15_P$15") (pintype "passive"))
      (node (ref "M-2") (pin "P$16") (pinfunction "16_P$16") (pintype "passive"))
      (node (ref "OBC") (pin "P$15") (pinfunction "15_P$15") (pintype "passive"))
      (node (ref "OBC") (pin "P$16") (pinfunction "16_P$16") (pintype "passive"))
      (node (ref "RAB") (pin "P$15") (pinfunction "15_P$15") (pintype "passive"))
      (node (ref "RAB") (pin "P$16") (pinfunction "16_P$16") (pintype "passive"))
    )
    (net (code "192") (name "SUP_UNREG_1") (class "Default")
      (node (ref "COM") (pin "P$23") (pinfunction "23_P$23") (pintype "passive"))
      (node (ref "COM") (pin "P$24") (pinfunction "24_P$24") (pintype "passive"))
      (node (ref "FAB") (pin "P$23") (pinfunction "23_P$23") (pintype "passive"))
      (node (ref "FAB") (pin "P$24") (pinfunction "24_P$24") (pintype "passive"))
      (node (ref "M-1") (pin "P$23") (pinfunction "23_P$23") (pintype "passive"))
      (node (ref "M-1") (pin "P$24") (pinfunction "24_P$24") (pintype "passive"))
      (node (ref "M-2") (pin "P$23") (pinfunction "23_P$23") (pintype "passive"))
      (node (ref "M-2") (pin "P$24") (pinfunction "24_P$24") (pintype "passive"))
      (node (ref "OBC") (pin "P$23") (pinfunction "23_P$23") (pintype "passive"))
      (node (ref "OBC") (pin "P$24") (pinfunction "24_P$24") (pintype "passive"))
      (node (ref "RAB") (pin "P$23") (pinfunction "23_P$23") (pintype "passive"))
      (node (ref "RAB") (pin "P$24") (pinfunction "24_P$24") (pintype "passive"))
    )
    (net (code "193") (name "SUP_UNREG_2") (class "Default")
      (node (ref "COM") (pin "P$35") (pinfunction "35_P$35") (pintype "passive"))
      (node (ref "COM") (pin "P$36") (pinfunction "36_P$36") (pintype "passive"))
      (node (ref "C_+X") (pin "3") (pinfunction "3_3") (pintype "passive"))
      (node (ref "C_+X") (pin "4") (pinfunction "4_4") (pintype "passive"))
      (node (ref "C_-Z") (pin "4") (pinfunction "4_4") (pintype "passive"))
      (node (ref "FAB") (pin "P$35") (pinfunction "35_P$35") (pintype "passive"))
      (node (ref "FAB") (pin "P$36") (pinfunction "36_P$36") (pintype "passive"))
      (node (ref "M-1") (pin "P$35") (pinfunction "35_P$35") (pintype "passive"))
      (node (ref "M-1") (pin "P$36") (pinfunction "36_P$36") (pintype "passive"))
      (node (ref "M-2") (pin "P$35") (pinfunction "35_P$35") (pintype "passive"))
      (node (ref "M-2") (pin "P$36") (pinfunction "36_P$36") (pintype "passive"))
      (node (ref "OBC") (pin "P$35") (pinfunction "35_P$35") (pintype "passive"))
      (node (ref "OBC") (pin "P$36") (pinfunction "36_P$36") (pintype "passive"))
      (node (ref "RAB") (pin "P$35") (pinfunction "35_P$35") (pintype "passive"))
      (node (ref "RAB") (pin "P$36") (pinfunction "36_P$36") (pintype "passive"))
    )
    (net (code "194") (name "TEMP_+X") (class "Default")
      (node (ref "C_+X") (pin "10") (pinfunction "10_10") (pintype "passive"))
      (node (ref "FAB") (pin "P$44") (pinfunction "44_P$44") (pintype "passive"))
    )
    (net (code "195") (name "TEMP_+Y") (class "Default")
      (node (ref "C_+Y") (pin "10") (pinfunction "10_10") (pintype "passive"))
      (node (ref "FAB") (pin "P$38") (pinfunction "38_P$38") (pintype "passive"))
    )
    (net (code "196") (name "TEMP_+Z") (class "Default")
      (node (ref "FAB") (pin "P$28") (pinfunction "28_P$28") (pintype "passive"))
    )
    (net (code "197") (name "TEMP_-X") (class "Default")
      (node (ref "C_-X") (pin "10") (pinfunction "10_10") (pintype "passive"))
      (node (ref "FAB") (pin "P$32") (pinfunction "32_P$32") (pintype "passive"))
    )
    (net (code "198") (name "TEMP_-Y") (class "Default")
      (node (ref "C_-Y") (pin "10") (pinfunction "10_10") (pintype "passive"))
      (node (ref "FAB") (pin "P$22") (pinfunction "22_P$22") (pintype "passive"))
    )
    (net (code "199") (name "TEMP_-Z") (class "Default")
      (node (ref "C_-Z") (pin "10") (pinfunction "10_10") (pintype "passive"))
      (node (ref "FAB") (pin "P$34") (pinfunction "34_P$34") (pintype "passive"))
    )
    (net (code "200") (name "UART(FAB2MAIN)") (class "Default")
      (node (ref "FAB") (pin "P$18") (pinfunction "18_P$18") (pintype "passive"))
      (node (ref "OBC") (pin "P$18") (pinfunction "18_P$18") (pintype "passive"))
    )
    (net (code "201") (name "UART(MAIN2FAB)") (class "Default")
      (node (ref "FAB") (pin "P$17") (pinfunction "17_P$17") (pintype "passive"))
      (node (ref "OBC") (pin "P$17") (pinfunction "17_P$17") (pintype "passive"))
    )
    (net (code "202") (name "UART(MAIN2MISSIONBOSS)") (class "Default")
      (node (ref "OBC") (pin "P$21") (pinfunction "21_P$21") (pintype "passive"))
      (node (ref "U_B") (pin "1") (pinfunction "1A_1") (pintype "input"))
    )
    (net (code "203") (name "UART(MAIN2MISSIONBOSS)B") (class "Default")
      (node (ref "P_18") (pin "21") (pinfunction "VREF+/AN3/RP3/RA3_21") (pintype "bidirectional"))
      (node (ref "U_B") (pin "6") (pinfunction "1Y_6") (pintype "output"))
    )
    (net (code "204") (name "UART(MISSIONBOSS2MAIN)") (class "Default")
      (node (ref "OBC") (pin "P$22") (pinfunction "22_P$22") (pintype "passive"))
      (node (ref "U_B") (pin "4") (pinfunction "2Y_4") (pintype "output"))
    )
    (net (code "205") (name "UART(MISSIONBOSS2MAIN)B") (class "Default")
      (node (ref "P_18") (pin "22") (pinfunction "SEG21/VREF-/AN2/RP2/RA2_22") (pintype "bidirectional"))
      (node (ref "U_B") (pin "3") (pinfunction "2A_3") (pintype "input"))
    )
    (net (code "206") (name "UART(OBC-COM1)") (class "Default")
      (node (ref "COM") (pin "P$7") (pinfunction "7_P$7") (pintype "passive"))
      (node (ref "OBC") (pin "P$7") (pinfunction "7_P$7") (pintype "passive"))
    )
    (net (code "207") (name "UART(OBC-COM2)") (class "Default")
      (node (ref "COM") (pin "P$8") (pinfunction "8_P$8") (pintype "passive"))
      (node (ref "OBC") (pin "P$8") (pinfunction "8_P$8") (pintype "passive"))
    )
    (net (code "208") (name "UART2(FAB2MAIN)") (class "Default")
      (node (ref "CPLD") (pin "15") (pinfunction "IOD6_15") (pintype "bidirectional"))
      (node (ref "FAB") (pin "P$20") (pinfunction "20_P$20") (pintype "passive"))
      (node (ref "OBC") (pin "P$20") (pinfunction "20_P$20") (pintype "passive"))
    )
    (net (code "209") (name "UART2(MAIN2FAB)") (class "Default")
      (node (ref "FAB") (pin "P$19") (pinfunction "19_P$19") (pintype "passive"))
      (node (ref "OBC") (pin "P$19") (pinfunction "19_P$19") (pintype "passive"))
    )
    (net (code "210") (name "unconnected-(COM-1-PadP$1)") (class "Default")
      (node (ref "COM") (pin "P$1") (pinfunction "1_P$1") (pintype "passive"))
    )
    (net (code "211") (name "unconnected-(COM-2-PadP$2)") (class "Default")
      (node (ref "COM") (pin "P$2") (pinfunction "2_P$2") (pintype "passive"))
    )
    (net (code "212") (name "unconnected-(COM-3-PadP$3)") (class "Default")
      (node (ref "COM") (pin "P$3") (pinfunction "3_P$3") (pintype "passive"))
    )
    (net (code "213") (name "unconnected-(COM-4-PadP$4)") (class "Default")
      (node (ref "COM") (pin "P$4") (pinfunction "4_P$4") (pintype "passive"))
    )
    (net (code "214") (name "unconnected-(COM-5-PadP$5)") (class "Default")
      (node (ref "COM") (pin "P$5") (pinfunction "5_P$5") (pintype "passive"))
    )
    (net (code "215") (name "unconnected-(COM-6-PadP$6)") (class "Default")
      (node (ref "COM") (pin "P$6") (pinfunction "6_P$6") (pintype "passive"))
    )
    (net (code "216") (name "unconnected-(COM-9-PadP$9)") (class "Default")
      (node (ref "COM") (pin "P$9") (pinfunction "9_P$9") (pintype "passive"))
    )
    (net (code "217") (name "unconnected-(COM-10-PadP$10)") (class "Default")
      (node (ref "COM") (pin "P$10") (pinfunction "10_P$10") (pintype "passive"))
    )
    (net (code "218") (name "unconnected-(COM-11-PadP$11)") (class "Default")
      (node (ref "COM") (pin "P$11") (pinfunction "11_P$11") (pintype "passive"))
    )
    (net (code "219") (name "unconnected-(COM-12-PadP$12)") (class "Default")
      (node (ref "COM") (pin "P$12") (pinfunction "12_P$12") (pintype "passive"))
    )
    (net (code "220") (name "unconnected-(COM-17-PadP$17)") (class "Default")
      (node (ref "COM") (pin "P$17") (pinfunction "17_P$17") (pintype "passive"))
    )
    (net (code "221") (name "unconnected-(COM-18-PadP$18)") (class "Default")
      (node (ref "COM") (pin "P$18") (pinfunction "18_P$18") (pintype "passive"))
    )
    (net (code "222") (name "unconnected-(COM-19-PadP$19)") (class "Default")
      (node (ref "COM") (pin "P$19") (pinfunction "19_P$19") (pintype "passive"))
    )
    (net (code "223") (name "unconnected-(COM-20-PadP$20)") (class "Default")
      (node (ref "COM") (pin "P$20") (pinfunction "20_P$20") (pintype "passive"))
    )
    (net (code "224") (name "unconnected-(COM-21-PadP$21)") (class "Default")
      (node (ref "COM") (pin "P$21") (pinfunction "21_P$21") (pintype "passive"))
    )
    (net (code "225") (name "unconnected-(COM-22-PadP$22)") (class "Default")
      (node (ref "COM") (pin "P$22") (pinfunction "22_P$22") (pintype "passive"))
    )
    (net (code "226") (name "unconnected-(COM-27-PadP$27)") (class "Default")
      (node (ref "COM") (pin "P$27") (pinfunction "27_P$27") (pintype "passive"))
    )
    (net (code "227") (name "unconnected-(COM-28-PadP$28)") (class "Default")
      (node (ref "COM") (pin "P$28") (pinfunction "28_P$28") (pintype "passive"))
    )
    (net (code "228") (name "unconnected-(COM-29-PadP$29)") (class "Default")
      (node (ref "COM") (pin "P$29") (pinfunction "29_P$29") (pintype "passive"))
    )
    (net (code "229") (name "unconnected-(COM-30-PadP$30)") (class "Default")
      (node (ref "COM") (pin "P$30") (pinfunction "30_P$30") (pintype "passive"))
    )
    (net (code "230") (name "unconnected-(COM-31-PadP$31)") (class "Default")
      (node (ref "COM") (pin "P$31") (pinfunction "31_P$31") (pintype "passive"))
    )
    (net (code "231") (name "unconnected-(COM-32-PadP$32)") (class "Default")
      (node (ref "COM") (pin "P$32") (pinfunction "32_P$32") (pintype "passive"))
    )
    (net (code "232") (name "unconnected-(COM-33-PadP$33)") (class "Default")
      (node (ref "COM") (pin "P$33") (pinfunction "33_P$33") (pintype "passive"))
    )
    (net (code "233") (name "unconnected-(COM-34-PadP$34)") (class "Default")
      (node (ref "COM") (pin "P$34") (pinfunction "34_P$34") (pintype "passive"))
    )
    (net (code "234") (name "unconnected-(COM-37-PadP$37)") (class "Default")
      (node (ref "COM") (pin "P$37") (pinfunction "37_P$37") (pintype "passive"))
    )
    (net (code "235") (name "unconnected-(COM-38-PadP$38)") (class "Default")
      (node (ref "COM") (pin "P$38") (pinfunction "38_P$38") (pintype "passive"))
    )
    (net (code "236") (name "unconnected-(COM-39-PadP$39)") (class "Default")
      (node (ref "COM") (pin "P$39") (pinfunction "39_P$39") (pintype "passive"))
    )
    (net (code "237") (name "unconnected-(COM-40-PadP$40)") (class "Default")
      (node (ref "COM") (pin "P$40") (pinfunction "40_P$40") (pintype "passive"))
    )
    (net (code "238") (name "unconnected-(COM-41-PadP$41)") (class "Default")
      (node (ref "COM") (pin "P$41") (pinfunction "41_P$41") (pintype "passive"))
    )
    (net (code "239") (name "unconnected-(COM-42-PadP$42)") (class "Default")
      (node (ref "COM") (pin "P$42") (pinfunction "42_P$42") (pintype "passive"))
    )
    (net (code "240") (name "unconnected-(CPLD-NC0-Pad18)") (class "Default")
      (node (ref "CPLD") (pin "18") (pinfunction "NC0_18") (pintype "passive"))
    )
    (net (code "241") (name "unconnected-(CPLD-NC1-Pad90)") (class "Default")
      (node (ref "CPLD") (pin "90") (pinfunction "NC1_90") (pintype "passive"))
    )
    (net (code "242") (name "unconnected-(C_+Y-Pad11)") (class "Default")
      (node (ref "C_+Y") (pin "11") (pinfunction "11_11") (pintype "passive"))
    )
    (net (code "243") (name "unconnected-(C_-X-Pad11)") (class "Default")
      (node (ref "C_-X") (pin "11") (pinfunction "11_11") (pintype "passive"))
    )
    (net (code "244") (name "unconnected-(C_-Y-Pad11)") (class "Default")
      (node (ref "C_-Y") (pin "11") (pinfunction "11_11") (pintype "passive"))
    )
    (net (code "245") (name "unconnected-(C_-Z-Pad11)") (class "Default")
      (node (ref "C_-Z") (pin "11") (pinfunction "11_11") (pintype "passive"))
    )
    (net (code "246") (name "unconnected-(FAB-45-PadP$45)") (class "Default")
      (node (ref "FAB") (pin "P$45") (pinfunction "45_P$45") (pintype "passive"))
    )
    (net (code "247") (name "unconnected-(FAB-46-PadP$46)") (class "Default")
      (node (ref "FAB") (pin "P$46") (pinfunction "46_P$46") (pintype "passive"))
    )
    (net (code "248") (name "unconnected-(FAB-47-PadP$47)") (class "Default")
      (node (ref "FAB") (pin "P$47") (pinfunction "47_P$47") (pintype "passive"))
    )
    (net (code "249") (name "unconnected-(M-1-37-PadP$37)") (class "Default")
      (node (ref "M-1") (pin "P$37") (pinfunction "37_P$37") (pintype "passive"))
    )
    (net (code "250") (name "unconnected-(M-1-38-PadP$38)") (class "Default")
      (node (ref "M-1") (pin "P$38") (pinfunction "38_P$38") (pintype "passive"))
    )
    (net (code "251") (name "unconnected-(M-1-39-PadP$39)") (class "Default")
      (node (ref "M-1") (pin "P$39") (pinfunction "39_P$39") (pintype "passive"))
    )
    (net (code "252") (name "unconnected-(M-1-40-PadP$40)") (class "Default")
      (node (ref "M-1") (pin "P$40") (pinfunction "40_P$40") (pintype "passive"))
    )
    (net (code "253") (name "unconnected-(P_18-COM0{slash}RP33{slash}REFO1{slash}RE3-Pad63)") (class "Default")
      (node (ref "P_18") (pin "63") (pinfunction "COM0/RP33/REFO1/RE3_63") (pintype "bidirectional"))
    )
    (net (code "254") (name "unconnected-(P_18-COM6{slash}SEG30{slash}AN18{slash}C3INA{slash}RP42{slash}RG2-Pad5)") (class "Default")
      (node (ref "P_18") (pin "5") (pinfunction "COM6/SEG30/AN18/C3INA/RP42/RG2_5") (pintype "bidirectional"))
    )
    (net (code "255") (name "unconnected-(P_18-COM7{slash}SEG31{slash}AN17{slash}C3INB{slash}RP43{slash}RG3-Pad6)") (class "Default")
      (node (ref "P_18") (pin "6") (pinfunction "COM7/SEG31/AN17/C3INB/RP43/RG3_6") (pintype "bidirectional"))
    )
    (net (code "256") (name "unconnected-(P_18-D+{slash}RF4-Pad14)") (class "Default")
      (node (ref "P_18") (pin "14") (pinfunction "D+/RF4_14") (pintype "bidirectional"))
    )
    (net (code "257") (name "unconnected-(P_18-D-{slash}RF3-Pad15)") (class "Default")
      (node (ref "P_18") (pin "15") (pinfunction "D-/RF3_15") (pintype "bidirectional"))
    )
    (net (code "258") (name "unconnected-(P_18-LCDBIAS3{slash}RP30{slash}~{CS}{slash}RE2-Pad64)") (class "Default")
      (node (ref "P_18") (pin "64") (pinfunction "LCDBIAS3/RP30/~{CS}/RE2_64") (pintype "bidirectional"))
    )
    (net (code "259") (name "unconnected-(P_18-OSC1{slash}CLKI{slash}RP10{slash}RA7-Pad39)") (class "Default")
      (node (ref "P_18") (pin "39") (pinfunction "OSC1/CLKI/RP10/RA7_39") (pintype "bidirectional"))
    )
    (net (code "260") (name "unconnected-(P_18-OSC2{slash}CLKO{slash}RP6{slash}RA6-Pad40)") (class "Default")
      (node (ref "P_18") (pin "40") (pinfunction "OSC2/CLKO/RP6/RA6_40") (pintype "bidirectional"))
    )
    (net (code "261") (name "unconnected-(P_18-SEG9{slash}RP14{slash}CTED1{slash}RB2-Pad46)") (class "Default")
      (node (ref "P_18") (pin "46") (pinfunction "SEG9/RP14/CTED1/RB2_46") (pintype "bidirectional"))
    )
    (net (code "262") (name "unconnected-(P_18-SEG10{slash}RP7{slash}CTED2{slash}RB3-Pad45)") (class "Default")
      (node (ref "P_18") (pin "45") (pinfunction "SEG10/RP7/CTED2/RB3_45") (pintype "bidirectional"))
    )
    (net (code "263") (name "unconnected-(P_18-SEG12{slash}RP16{slash}CTED10{slash}RC5-Pad36)") (class "Default")
      (node (ref "P_18") (pin "36") (pinfunction "SEG12/RP16/CTED10/RC5_36") (pintype "bidirectional"))
    )
    (net (code "264") (name "unconnected-(P_18-SEG13{slash}AN9{slash}RP11{slash}CTED7{slash}RC2-Pad33)") (class "Default")
      (node (ref "P_18") (pin "33") (pinfunction "SEG13/AN9/RP11/CTED7/RC2_33") (pintype "bidirectional"))
    )
    (net (code "265") (name "unconnected-(P_18-SEG15{slash}AN4{slash}LVDIN{slash}C1INA{slash}C2INA{slash}C3INA{slash}RP5{slash}RA5-Pad27)") (class "Default")
      (node (ref "P_18") (pin "27") (pinfunction "SEG15/AN4/LVDIN/C1INA/C2INA/C3INA/RP5/RA5_27") (pintype "bidirectional"))
    )
    (net (code "266") (name "unconnected-(P_18-SEG26{slash}AN16{slash}C3INC{slash}RP44{slash}RTCC{slash}RG4-Pad8)") (class "Default")
      (node (ref "P_18") (pin "8") (pinfunction "SEG26/AN16/C3INC/RP44/RTCC/RG4_8") (pintype "bidirectional"))
    )
    (net (code "267") (name "unconnected-(P_18-SEG27{slash}RP18{slash}~{UOE}{slash}CTED11{slash}RC6-Pad31)") (class "Default")
      (node (ref "P_18") (pin "31") (pinfunction "SEG27/RP18/~{UOE}/CTED11/RC6_31") (pintype "bidirectional"))
    )
    (net (code "268") (name "unconnected-(P_18-SOSCI{slash}RC1-Pad29)") (class "Default")
      (node (ref "P_18") (pin "29") (pinfunction "SOSCI/RC1_29") (pintype "bidirectional"))
    )
    (net (code "269") (name "unconnected-(P_18-SOSCO{slash}SCLKI{slash}PWRLCLK{slash}RC0-Pad30)") (class "Default")
      (node (ref "P_18") (pin "30") (pinfunction "SOSCO/SCLKI/PWRLCLK/RC0_30") (pintype "bidirectional"))
    )
    (net (code "270") (name "unconnected-(P_18-VBAT-Pad18)") (class "Default")
      (node (ref "P_18") (pin "18") (pinfunction "VBAT_18") (pintype "bidirectional"))
    )
    (net (code "271") (name "unconnected-(SW0-P$2-Pad2)") (class "Default")
      (node (ref "SW0") (pin "2") (pinfunction "P$2_2") (pintype "bidirectional"))
    )
    (net (code "272") (name "unconnected-(U1-GATEP-Pad3)") (class "Default")
      (node (ref "U1") (pin "3") (pinfunction "GATEP_3") (pintype "passive"))
    )
    (net (code "273") (name "unconnected-(U1-~{PWRGD}-Pad8)") (class "Default")
      (node (ref "U1") (pin "8") (pinfunction "~{PWRGD}_8") (pintype "output"))
    )
  )
)
